# ARE_adaptadores.net
KiCad netlist of a schematic drawn in EAGLE
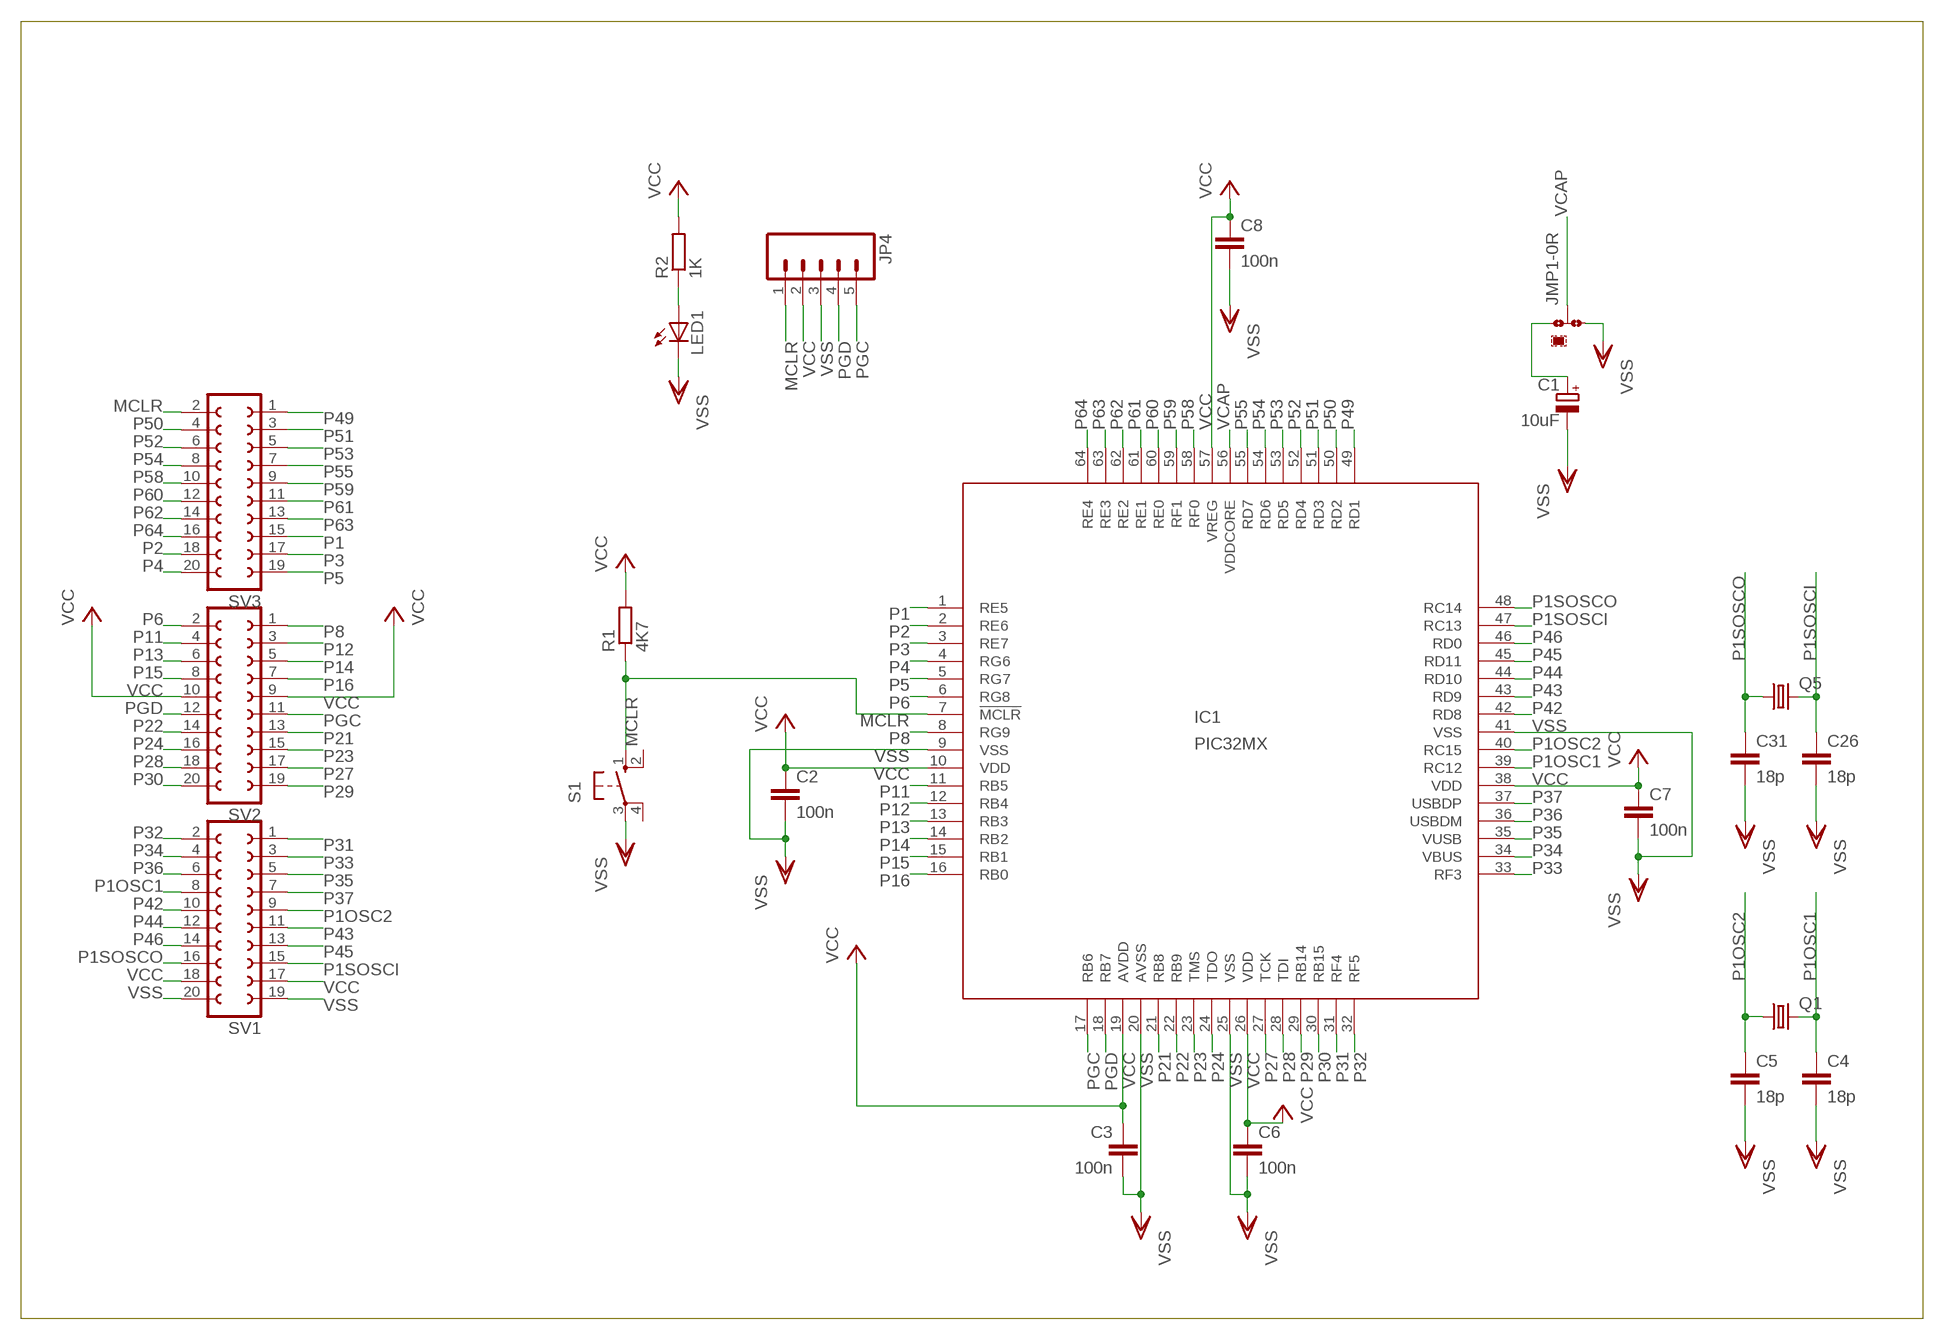
[diagram p0: schematic, sheet 1]
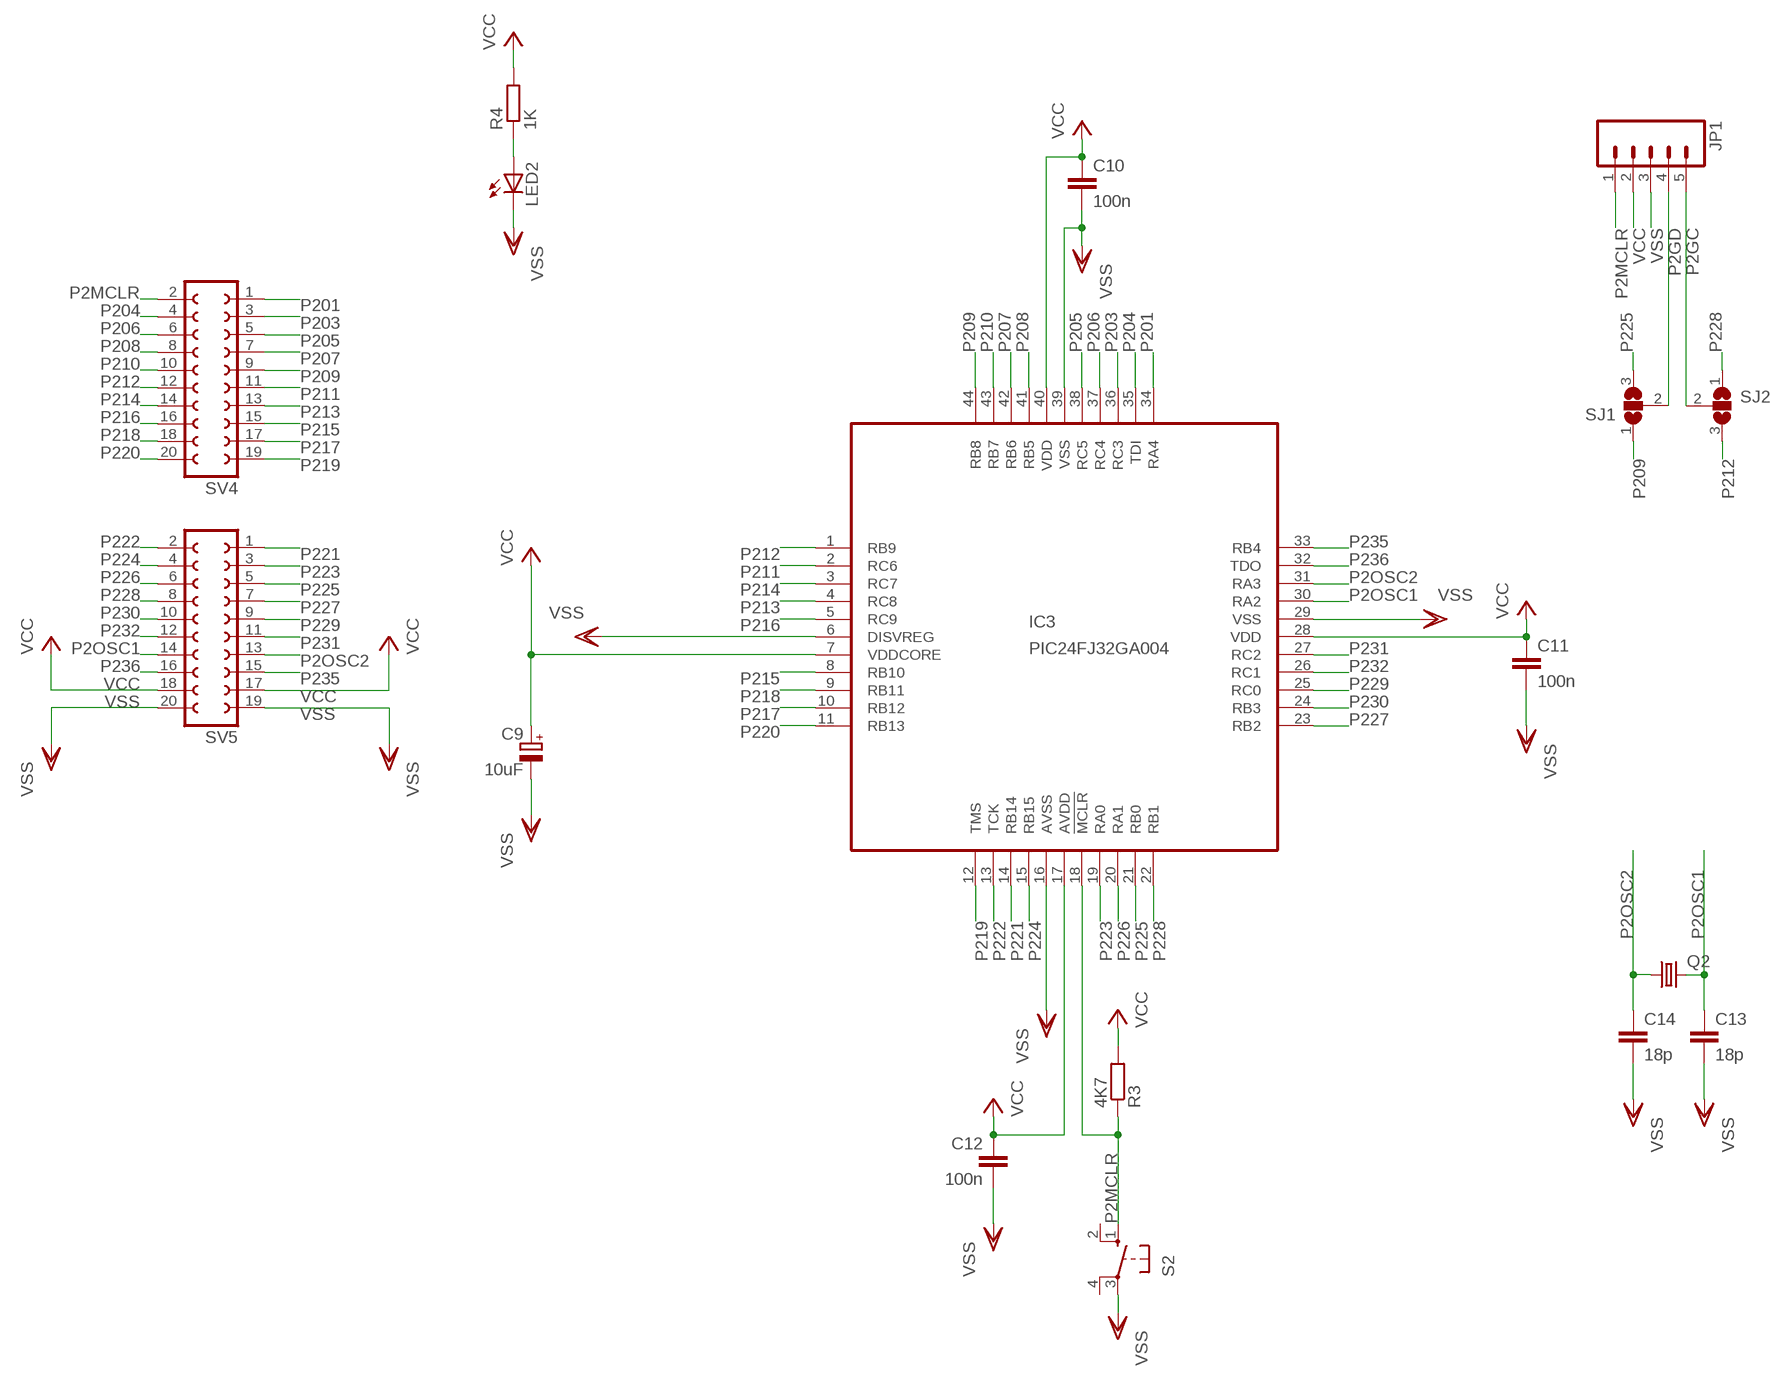
[diagram p1: schematic, sheet 2]
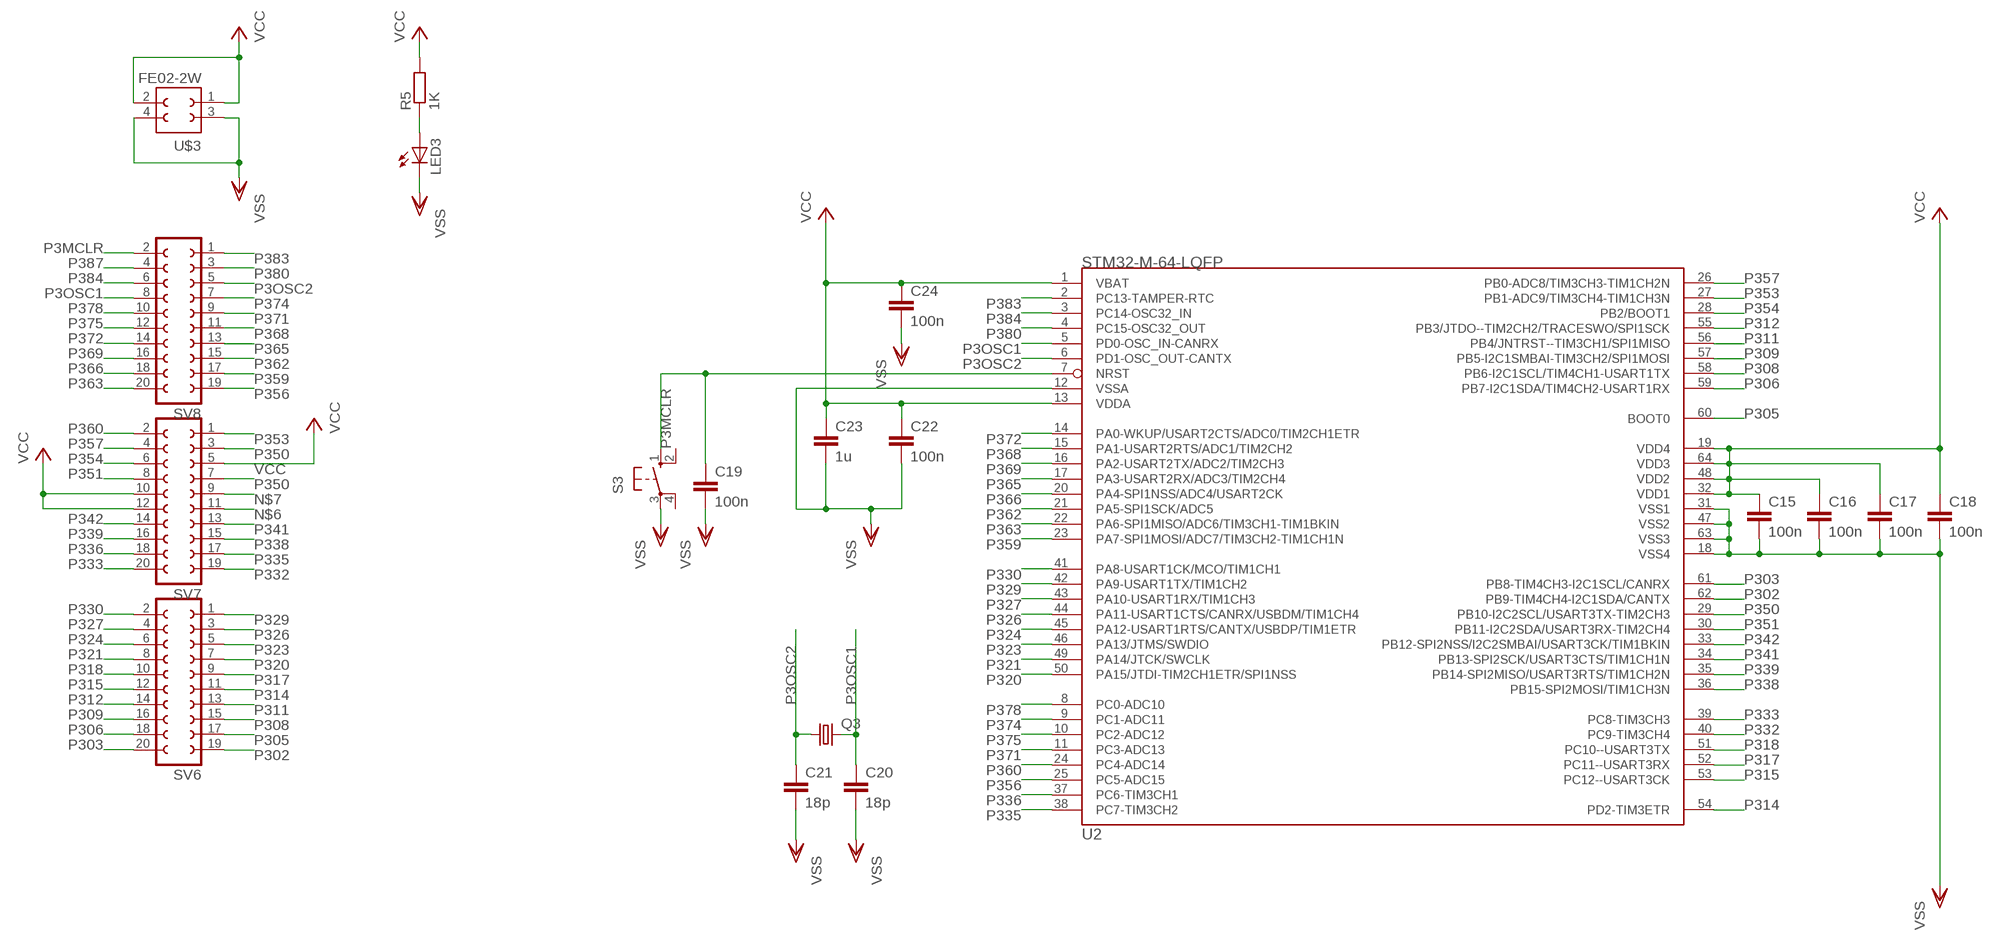
[diagram p2: schematic, sheet 3]
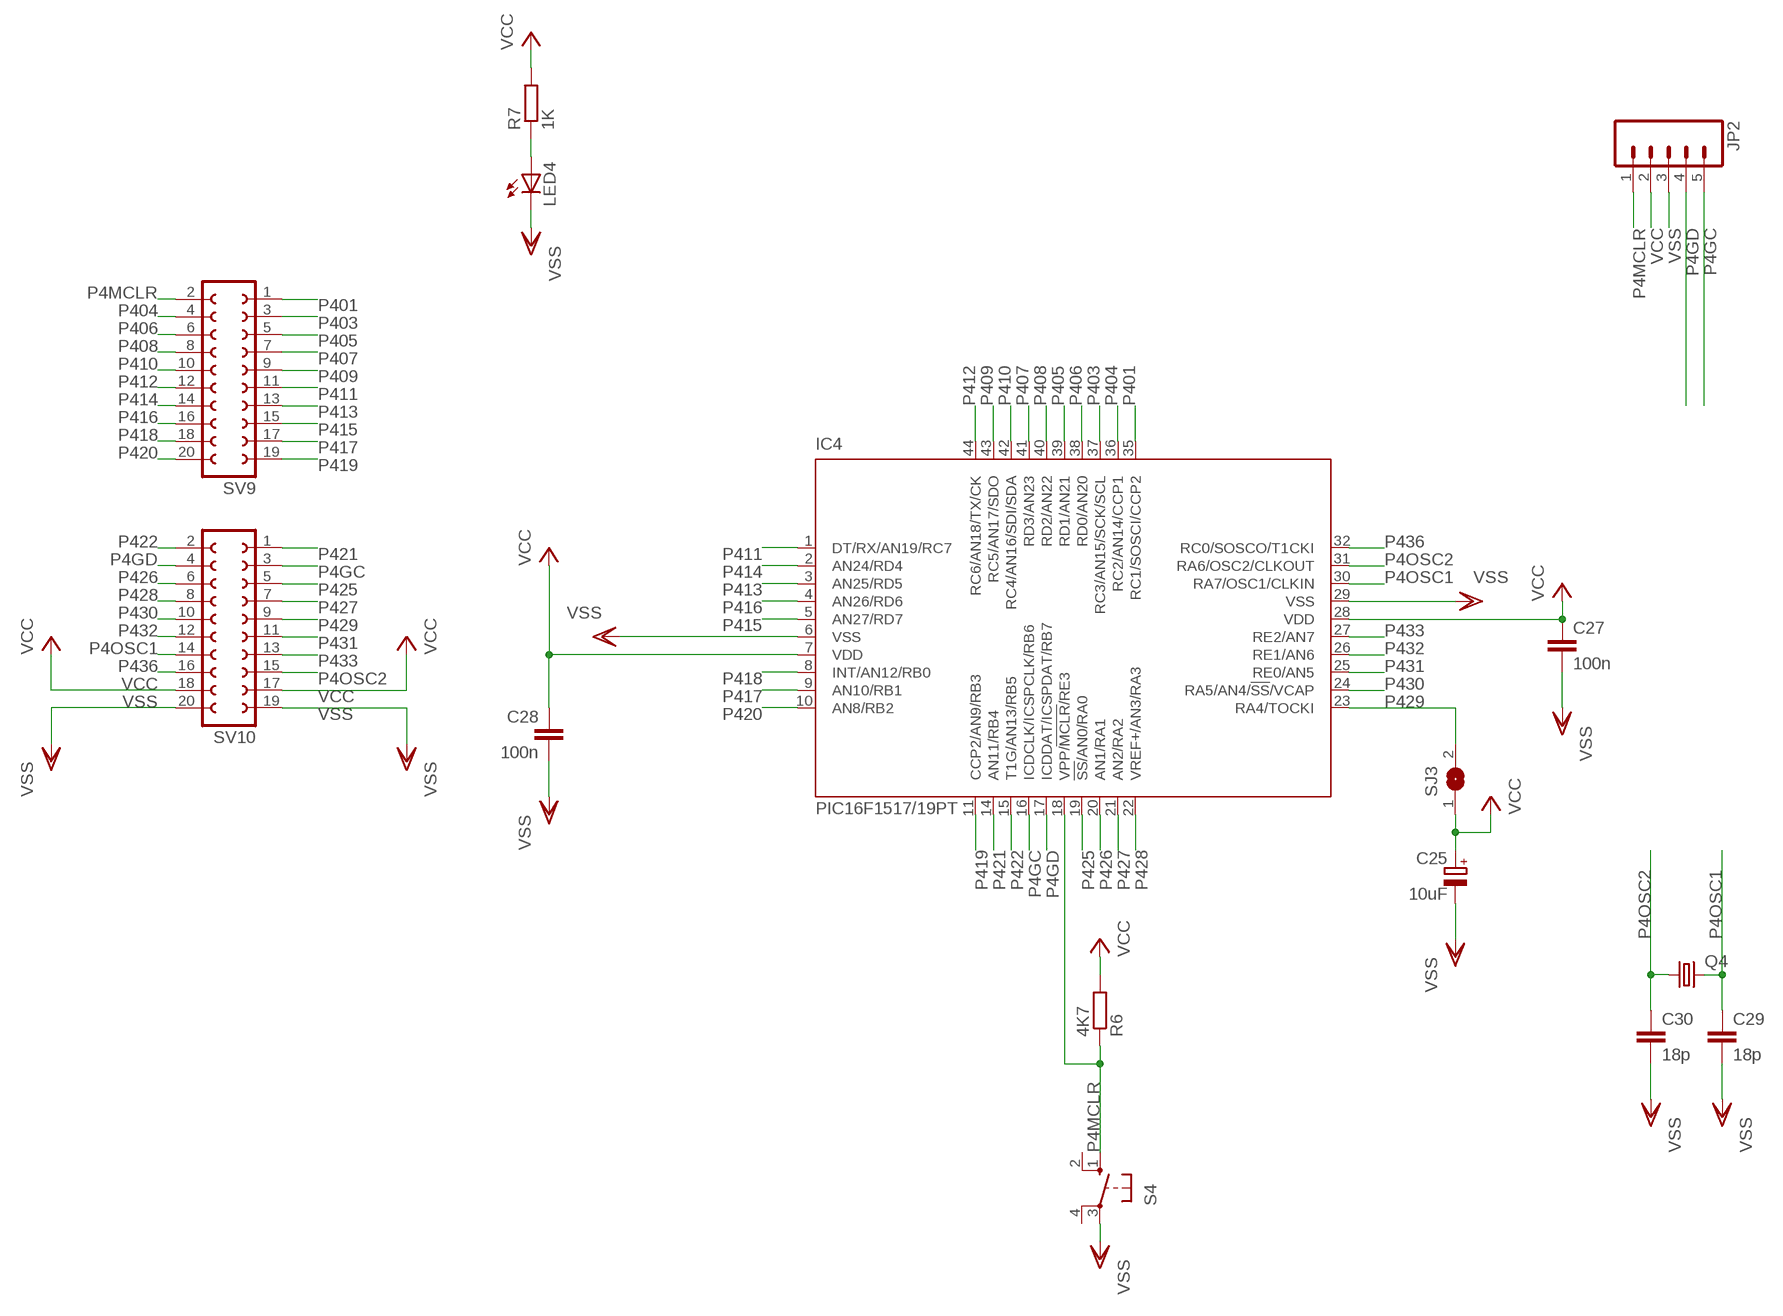
[diagram p3: schematic, sheet 4]
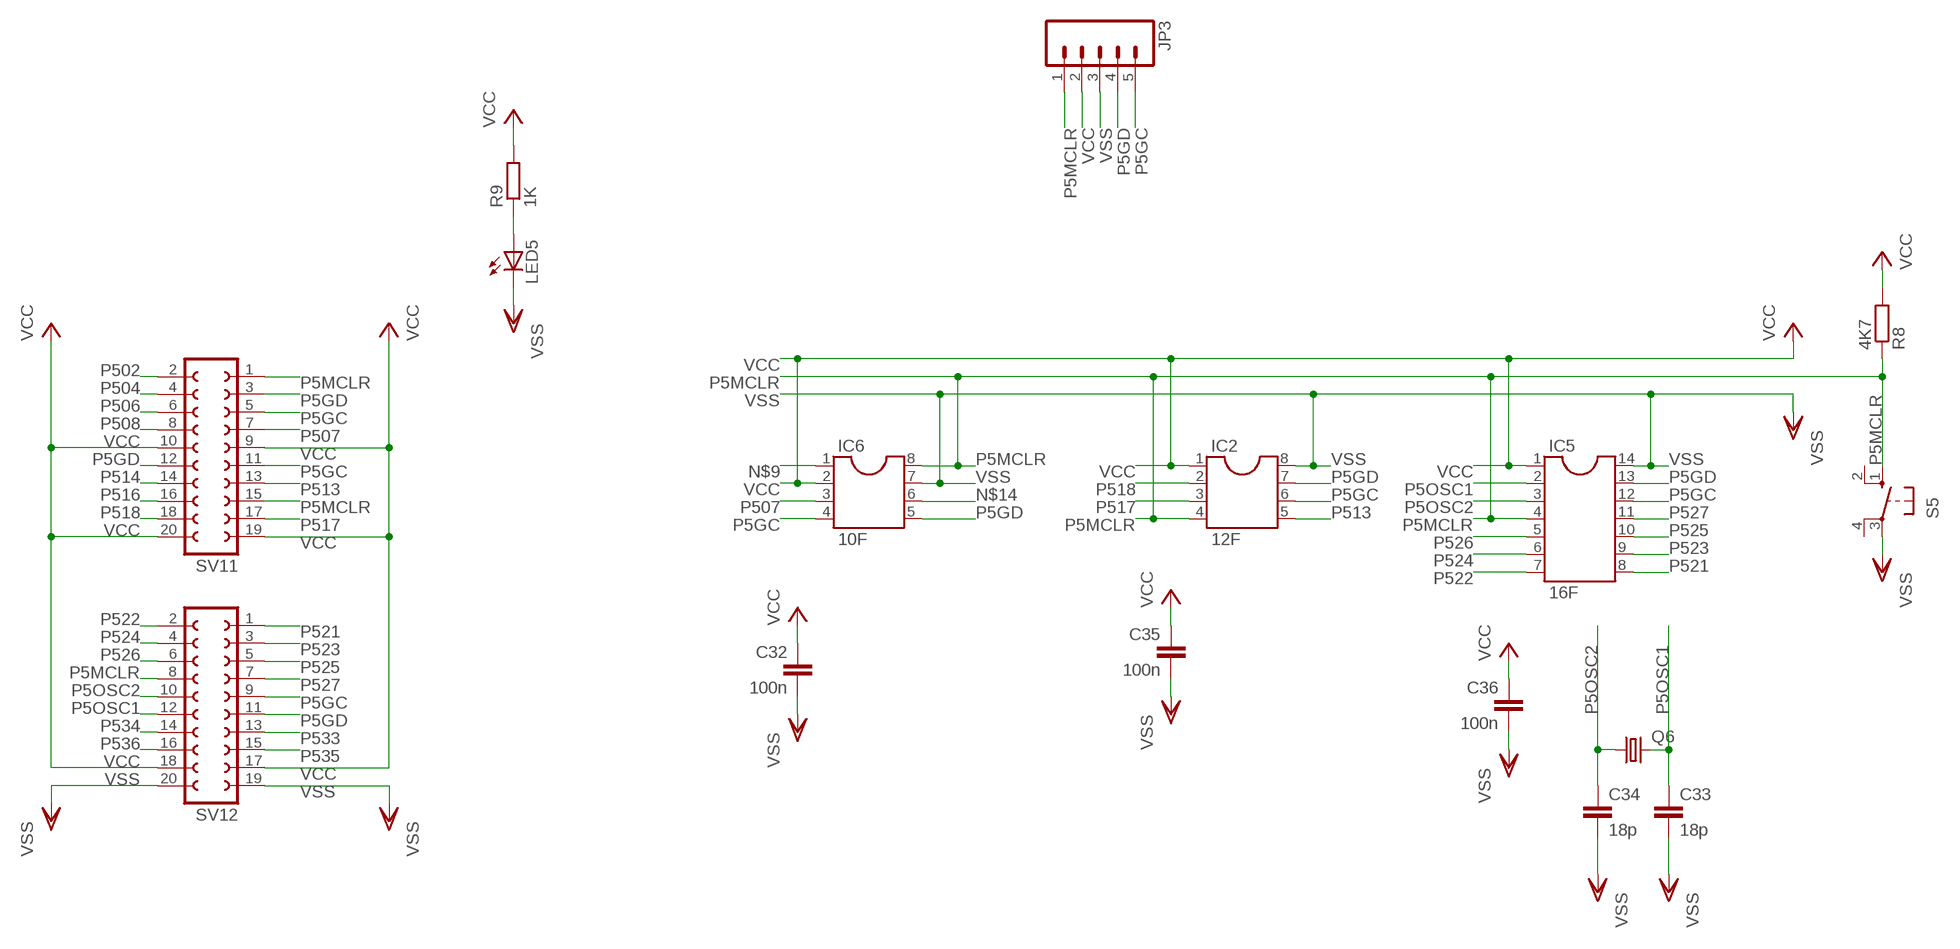
[diagram p4: schematic, sheet 5]

(export (version "E")
  (design (tool "Eeschema 10.0.6"))
  (components
    (comp (ref "C1")
      (value "10uF")
      (footprint "eagle-import:SMC_C")
      (libsource (lib "eagle-import") (part "CPOL-EUSMCC"))
    )
    (comp (ref "C2")
      (value "100n")
      (footprint "eagle-import:C0805")
      (libsource (lib "eagle-import") (part "C-EUC0805"))
    )
    (comp (ref "C3")
      (value "100n")
      (footprint "eagle-import:C0805")
      (libsource (lib "eagle-import") (part "C-EUC0805"))
    )
    (comp (ref "C4")
      (value "18p")
      (footprint "eagle-import:C0805")
      (libsource (lib "eagle-import") (part "C-EUC0805"))
    )
    (comp (ref "C5")
      (value "18p")
      (footprint "eagle-import:C0805")
      (libsource (lib "eagle-import") (part "C-EUC0805"))
    )
    (comp (ref "C6")
      (value "100n")
      (footprint "eagle-import:C0805")
      (libsource (lib "eagle-import") (part "C-EUC0805"))
    )
    (comp (ref "C7")
      (value "100n")
      (footprint "eagle-import:C0805")
      (libsource (lib "eagle-import") (part "C-EUC0805"))
    )
    (comp (ref "C8")
      (value "100n")
      (footprint "eagle-import:C0805")
      (libsource (lib "eagle-import") (part "C-EUC0805"))
    )
    (comp (ref "C26")
      (value "18p")
      (footprint "eagle-import:C0805")
      (libsource (lib "eagle-import") (part "C-EUC0805"))
    )
    (comp (ref "C31")
      (value "18p")
      (footprint "eagle-import:C0805")
      (libsource (lib "eagle-import") (part "C-EUC0805"))
    )
    (comp (ref "IC1")
      (value "PIC32MX")
      (footprint "eagle-import:TQFP64-10X10")
      (libsource (lib "eagle-import") (part "PIC32MX440F256H"))
    )
    (comp (ref "JMP1")
      (value "0R-JUMPA")
      (footprint "eagle-import:A0R-JMP")
      (libsource (lib "eagle-import") (part "0R-JUMPA"))
    )
    (comp (ref "JP4")
      (value "M05PTH")
      (footprint "eagle-import:1X05")
      (libsource (lib "eagle-import") (part "M05PTH"))
    )
    (comp (ref "LED1")
      (value "LEDCHIPLED_0805")
      (footprint "eagle-import:CHIPLED_0805")
      (libsource (lib "eagle-import") (part "LEDCHIPLED_0805"))
    )
    (comp (ref "Q1")
      (value "CRYSTALHC18U-V")
      (footprint "eagle-import:HC18U-V")
      (libsource (lib "eagle-import") (part "CRYSTALHC18U-V"))
    )
    (comp (ref "Q5")
      (value "CRYSTALHC18U-V")
      (footprint "eagle-import:HC18U-V")
      (libsource (lib "eagle-import") (part "CRYSTALHC18U-V"))
    )
    (comp (ref "R1")
      (value "4K7")
      (footprint "eagle-import:R0805")
      (libsource (lib "eagle-import") (part "R-EU_R0805"))
    )
    (comp (ref "R2")
      (value "1K")
      (footprint "eagle-import:R0805")
      (libsource (lib "eagle-import") (part "R-EU_R0805"))
    )
    (comp (ref "S1")
      (value "10-XX")
      (footprint "eagle-import:B3F-10XX")
      (fields
        (field (name "MPN") "B3F-1000")
        (field (name "MPN_1") "B3F-1000")
        (field (name "OC_FARNELL") "176432")
        (field (name "OC_NEWARK") "36M3542")
      )
      (libsource (lib "eagle-import") (part "10-XX"))
    )
    (comp (ref "SV1")
      (value "FE10-2W")
      (footprint "eagle-import:FE10-2W")
      (libsource (lib "eagle-import") (part "FE10-2W"))
    )
    (comp (ref "SV2")
      (value "FE10-2W")
      (footprint "eagle-import:FE10-2W")
      (libsource (lib "eagle-import") (part "FE10-2W"))
    )
    (comp (ref "SV3")
      (value "FE10-2W")
      (footprint "eagle-import:FE10-2W")
      (libsource (lib "eagle-import") (part "FE10-2W"))
    )
    (comp (ref "C15")
      (value "100n")
      (footprint "eagle-import:C0805")
      (libsource (lib "eagle-import") (part "C-EUC0805"))
    )
    (comp (ref "C16")
      (value "100n")
      (footprint "eagle-import:C0805")
      (libsource (lib "eagle-import") (part "C-EUC0805"))
    )
    (comp (ref "C17")
      (value "100n")
      (footprint "eagle-import:C0805")
      (libsource (lib "eagle-import") (part "C-EUC0805"))
    )
    (comp (ref "C18")
      (value "100n")
      (footprint "eagle-import:C0805")
      (libsource (lib "eagle-import") (part "C-EUC0805"))
    )
    (comp (ref "C19")
      (value "100n")
      (footprint "eagle-import:C0805")
      (libsource (lib "eagle-import") (part "C-EUC0805"))
    )
    (comp (ref "C20")
      (value "18p")
      (footprint "eagle-import:C0805")
      (libsource (lib "eagle-import") (part "C-EUC0805"))
    )
    (comp (ref "C21")
      (value "18p")
      (footprint "eagle-import:C0805")
      (libsource (lib "eagle-import") (part "C-EUC0805"))
    )
    (comp (ref "C22")
      (value "100n")
      (footprint "eagle-import:C0805")
      (libsource (lib "eagle-import") (part "C-EUC0805"))
    )
    (comp (ref "C23")
      (value "1u")
      (footprint "eagle-import:C0805")
      (libsource (lib "eagle-import") (part "C-EUC0805"))
    )
    (comp (ref "C24")
      (value "100n")
      (footprint "eagle-import:C0805")
      (libsource (lib "eagle-import") (part "C-EUC0805"))
    )
    (comp (ref "LED3")
      (value "LEDCHIPLED_0805")
      (footprint "eagle-import:CHIPLED_0805")
      (libsource (lib "eagle-import") (part "LEDCHIPLED_0805"))
    )
    (comp (ref "Q3")
      (value "CRYSTALHC18U-V")
      (footprint "eagle-import:HC18U-V")
      (libsource (lib "eagle-import") (part "CRYSTALHC18U-V"))
    )
    (comp (ref "R5")
      (value "1K")
      (footprint "eagle-import:R0805")
      (libsource (lib "eagle-import") (part "R-EU_R0805"))
    )
    (comp (ref "S3")
      (value "10-XX")
      (footprint "eagle-import:B3F-10XX")
      (fields
        (field (name "MPN") "B3F-1000")
        (field (name "MPN_1") "B3F-1000")
        (field (name "OC_FARNELL") "176432")
        (field (name "OC_NEWARK") "36M3542")
      )
      (libsource (lib "eagle-import") (part "10-XX"))
    )
    (comp (ref "SV6")
      (value "FE10-2W")
      (footprint "eagle-import:FE10-2W")
      (libsource (lib "eagle-import") (part "FE10-2W"))
    )
    (comp (ref "SV7")
      (value "FE10-2W")
      (footprint "eagle-import:FE10-2W")
      (libsource (lib "eagle-import") (part "FE10-2W"))
    )
    (comp (ref "SV8")
      (value "FE10-2W")
      (footprint "eagle-import:FE10-2W")
      (libsource (lib "eagle-import") (part "FE10-2W"))
    )
    (comp (ref "U$3")
      (value "FE02-2W")
      (footprint "eagle-import:FE02-2W")
      (libsource (lib "eagle-import") (part "FE02-2W"))
    )
    (comp (ref "U2")
      (value "STM32-M-64-LQFP")
      (footprint "eagle-import:LQFP64")
      (libsource (lib "eagle-import") (part "STM32-M-64-LQFP"))
    )
    (comp (ref "C25")
      (value "10uF")
      (footprint "eagle-import:SMC_C")
      (libsource (lib "eagle-import") (part "CPOL-EUSMCC"))
    )
    (comp (ref "C27")
      (value "100n")
      (footprint "eagle-import:C0805")
      (libsource (lib "eagle-import") (part "C-EUC0805"))
    )
    (comp (ref "C28")
      (value "100n")
      (footprint "eagle-import:C0805")
      (libsource (lib "eagle-import") (part "C-EUC0805"))
    )
    (comp (ref "C29")
      (value "18p")
      (footprint "eagle-import:C0805")
      (libsource (lib "eagle-import") (part "C-EUC0805"))
    )
    (comp (ref "C30")
      (value "18p")
      (footprint "eagle-import:C0805")
      (libsource (lib "eagle-import") (part "C-EUC0805"))
    )
    (comp (ref "IC4")
      (value "PIC16F1517/19PT")
      (footprint "eagle-import:TQFP44")
      (libsource (lib "eagle-import") (part "PIC16F1517/19PT"))
    )
    (comp (ref "JP2")
      (value "M05PTH")
      (footprint "eagle-import:1X05")
      (libsource (lib "eagle-import") (part "M05PTH"))
    )
    (comp (ref "LED4")
      (value "LEDCHIPLED_0805")
      (footprint "eagle-import:CHIPLED_0805")
      (libsource (lib "eagle-import") (part "LEDCHIPLED_0805"))
    )
    (comp (ref "Q4")
      (value "CRYSTALHC18U-V")
      (footprint "eagle-import:HC18U-V")
      (libsource (lib "eagle-import") (part "CRYSTALHC18U-V"))
    )
    (comp (ref "R6")
      (value "4K7")
      (footprint "eagle-import:R0805")
      (libsource (lib "eagle-import") (part "R-EU_R0805"))
    )
    (comp (ref "R7")
      (value "1K")
      (footprint "eagle-import:R0805")
      (libsource (lib "eagle-import") (part "R-EU_R0805"))
    )
    (comp (ref "S4")
      (value "10-XX")
      (footprint "eagle-import:B3F-10XX")
      (fields
        (field (name "MPN") "B3F-1000")
        (field (name "MPN_1") "B3F-1000")
        (field (name "OC_FARNELL") "176432")
        (field (name "OC_NEWARK") "36M3542")
      )
      (libsource (lib "eagle-import") (part "10-XX"))
    )
    (comp (ref "SJ3") (value "SJ") (footprint "eagle-import:SJ") (libsource (lib "eagle-import") (part "SJ")))
    (comp (ref "SV9")
      (value "FE10-2W")
      (footprint "eagle-import:FE10-2W")
      (libsource (lib "eagle-import") (part "FE10-2W"))
    )
    (comp (ref "SV10")
      (value "FE10-2W")
      (footprint "eagle-import:FE10-2W")
      (libsource (lib "eagle-import") (part "FE10-2W"))
    )
    (comp (ref "C32")
      (value "100n")
      (footprint "eagle-import:C0805")
      (libsource (lib "eagle-import") (part "C-EUC0805"))
    )
    (comp (ref "C33")
      (value "18p")
      (footprint "eagle-import:C0805")
      (libsource (lib "eagle-import") (part "C-EUC0805"))
    )
    (comp (ref "C34")
      (value "18p")
      (footprint "eagle-import:C0805")
      (libsource (lib "eagle-import") (part "C-EUC0805"))
    )
    (comp (ref "C35")
      (value "100n")
      (footprint "eagle-import:C0805")
      (libsource (lib "eagle-import") (part "C-EUC0805"))
    )
    (comp (ref "C36")
      (value "100n")
      (footprint "eagle-import:C0805")
      (libsource (lib "eagle-import") (part "C-EUC0805"))
    )
    (comp (ref "IC2")
      (value "12F")
      (footprint "eagle-import:SOCKET-08")
      (libsource (lib "eagle-import") (part "DIL8S"))
    )
    (comp (ref "IC5")
      (value "16F")
      (footprint "eagle-import:SOCKET-14")
      (libsource (lib "eagle-import") (part "DIL14S"))
    )
    (comp (ref "IC6")
      (value "10F")
      (footprint "eagle-import:SOCKET-08")
      (libsource (lib "eagle-import") (part "DIL8S"))
    )
    (comp (ref "JP3")
      (value "M05PTH")
      (footprint "eagle-import:1X05")
      (libsource (lib "eagle-import") (part "M05PTH"))
    )
    (comp (ref "LED5")
      (value "LEDCHIPLED_0805")
      (footprint "eagle-import:CHIPLED_0805")
      (libsource (lib "eagle-import") (part "LEDCHIPLED_0805"))
    )
    (comp (ref "Q6")
      (value "CRYSTALHC18U-V")
      (footprint "eagle-import:HC18U-V")
      (libsource (lib "eagle-import") (part "CRYSTALHC18U-V"))
    )
    (comp (ref "R8")
      (value "4K7")
      (footprint "eagle-import:R0805")
      (libsource (lib "eagle-import") (part "R-EU_R0805"))
    )
    (comp (ref "R9")
      (value "1K")
      (footprint "eagle-import:R0805")
      (libsource (lib "eagle-import") (part "R-EU_R0805"))
    )
    (comp (ref "S5")
      (value "10-XX")
      (footprint "eagle-import:B3F-10XX")
      (fields
        (field (name "MPN") "B3F-1000")
        (field (name "MPN_1") "B3F-1000")
        (field (name "OC_FARNELL") "176432")
        (field (name "OC_NEWARK") "36M3542")
      )
      (libsource (lib "eagle-import") (part "10-XX"))
    )
    (comp (ref "SV11")
      (value "FE10-2W")
      (footprint "eagle-import:FE10-2W")
      (libsource (lib "eagle-import") (part "FE10-2W"))
    )
    (comp (ref "SV12")
      (value "FE10-2W")
      (footprint "eagle-import:FE10-2W")
      (libsource (lib "eagle-import") (part "FE10-2W"))
    )
    (comp (ref "C9")
      (value "10uF")
      (footprint "eagle-import:SMC_C")
      (libsource (lib "eagle-import") (part "CPOL-EUSMCC"))
    )
    (comp (ref "C10")
      (value "100n")
      (footprint "eagle-import:C0805")
      (libsource (lib "eagle-import") (part "C-EUC0805"))
    )
    (comp (ref "C11")
      (value "100n")
      (footprint "eagle-import:C0805")
      (libsource (lib "eagle-import") (part "C-EUC0805"))
    )
    (comp (ref "C12")
      (value "100n")
      (footprint "eagle-import:C0805")
      (libsource (lib "eagle-import") (part "C-EUC0805"))
    )
    (comp (ref "C13")
      (value "18p")
      (footprint "eagle-import:C0805")
      (libsource (lib "eagle-import") (part "C-EUC0805"))
    )
    (comp (ref "C14")
      (value "18p")
      (footprint "eagle-import:C0805")
      (libsource (lib "eagle-import") (part "C-EUC0805"))
    )
    (comp (ref "IC3")
      (value "PIC24FJ32GA004")
      (footprint "eagle-import:TQFP44")
      (fields (field (name "MPN") "PIC24FJ32GA004-E/PT"))
      (libsource (lib "eagle-import") (part "PIC24FJ32GA004"))
    )
    (comp (ref "JP1")
      (value "M05PTH")
      (footprint "eagle-import:1X05")
      (libsource (lib "eagle-import") (part "M05PTH"))
    )
    (comp (ref "LED2")
      (value "LEDCHIPLED_0805")
      (footprint "eagle-import:CHIPLED_0805")
      (libsource (lib "eagle-import") (part "LEDCHIPLED_0805"))
    )
    (comp (ref "Q2")
      (value "CRYSTALHC18U-V")
      (footprint "eagle-import:HC18U-V")
      (libsource (lib "eagle-import") (part "CRYSTALHC18U-V"))
    )
    (comp (ref "R3")
      (value "4K7")
      (footprint "eagle-import:R0805")
      (libsource (lib "eagle-import") (part "R-EU_R0805"))
    )
    (comp (ref "R4")
      (value "1K")
      (footprint "eagle-import:R0805")
      (libsource (lib "eagle-import") (part "R-EU_R0805"))
    )
    (comp (ref "S2")
      (value "10-XX")
      (footprint "eagle-import:B3F-10XX")
      (fields
        (field (name "MPN") "B3F-1000")
        (field (name "MPN_1") "B3F-1000")
        (field (name "OC_FARNELL") "176432")
        (field (name "OC_NEWARK") "36M3542")
      )
      (libsource (lib "eagle-import") (part "10-XX"))
    )
    (comp (ref "SJ1")
      (value "SJ2W")
      (footprint "eagle-import:SJ_2")
      (libsource (lib "eagle-import") (part "SJ2W"))
    )
    (comp (ref "SJ2")
      (value "SJ2W")
      (footprint "eagle-import:SJ_2")
      (libsource (lib "eagle-import") (part "SJ2W"))
    )
    (comp (ref "SV4")
      (value "FE10-2W")
      (footprint "eagle-import:FE10-2W")
      (libsource (lib "eagle-import") (part "FE10-2W"))
    )
    (comp (ref "SV5")
      (value "FE10-2W")
      (footprint "eagle-import:FE10-2W")
      (libsource (lib "eagle-import") (part "FE10-2W"))
    )
  )
  (nets
    (net (code "1") (name "MCLR") (class "Default")
      (node (ref "IC1") (pin "7") (pinfunction "~{MCLR}_7") (pintype "input"))
      (node (ref "JP4") (pin "1") (pinfunction "1_1") (pintype "passive"))
      (node (ref "R1") (pin "1") (pinfunction "1_1") (pintype "passive"))
      (node (ref "S1") (pin "1") (pinfunction "S_1") (pintype "passive"))
      (node (ref "SV3") (pin "2") (pinfunction "2_2") (pintype "passive"))
    )
    (net (code "2") (name "N$6") (class "Default")
      (node (ref "SV7") (pin "11") (pinfunction "11_11") (pintype "passive"))
    )
    (net (code "3") (name "N$7") (class "Default")
      (node (ref "SV7") (pin "9") (pinfunction "9_9") (pintype "passive"))
    )
    (net (code "4") (name "N$9") (class "Default")
      (node (ref "IC6") (pin "1") (pinfunction "1_1") (pintype "passive"))
    )
    (net (code "5") (name "N$14") (class "Default")
      (node (ref "IC6") (pin "6") (pinfunction "6_6") (pintype "passive"))
    )
    (net (code "6") (name "Net-(C1-Pad+)") (class "Default")
      (node (ref "C1") (pin "+") (pinfunction "+_+") (pintype "passive"))
      (node (ref "JMP1") (pin "1") (pinfunction "1_1") (pintype "passive"))
    )
    (net (code "7") (name "Net-(LED1-PadA)") (class "Default")
      (node (ref "LED1") (pin "A") (pinfunction "A_A") (pintype "passive"))
      (node (ref "R2") (pin "1") (pinfunction "1_1") (pintype "passive"))
    )
    (net (code "8") (name "Net-(LED2-PadA)") (class "Default")
      (node (ref "LED2") (pin "A") (pinfunction "A_A") (pintype "passive"))
      (node (ref "R4") (pin "1") (pinfunction "1_1") (pintype "passive"))
    )
    (net (code "9") (name "Net-(LED3-PadA)") (class "Default")
      (node (ref "LED3") (pin "A") (pinfunction "A_A") (pintype "passive"))
      (node (ref "R5") (pin "1") (pinfunction "1_1") (pintype "passive"))
    )
    (net (code "10") (name "Net-(LED4-PadA)") (class "Default")
      (node (ref "LED4") (pin "A") (pinfunction "A_A") (pintype "passive"))
      (node (ref "R7") (pin "1") (pinfunction "1_1") (pintype "passive"))
    )
    (net (code "11") (name "Net-(LED5-PadA)") (class "Default")
      (node (ref "LED5") (pin "A") (pinfunction "A_A") (pintype "passive"))
      (node (ref "R9") (pin "1") (pinfunction "1_1") (pintype "passive"))
    )
    (net (code "12") (name "P1") (class "Default")
      (node (ref "IC1") (pin "1") (pinfunction "RE5_1") (pintype "bidirectional"))
      (node (ref "SV3") (pin "15") (pinfunction "15_15") (pintype "passive"))
    )
    (net (code "13") (name "P1OSC1") (class "Default")
      (node (ref "C4") (pin "1") (pinfunction "1_1") (pintype "passive"))
      (node (ref "IC1") (pin "39") (pinfunction "RC12_39") (pintype "bidirectional"))
      (node (ref "Q1") (pin "2") (pinfunction "2_2") (pintype "passive"))
      (node (ref "SV1") (pin "8") (pinfunction "8_8") (pintype "passive"))
    )
    (net (code "14") (name "P1OSC2") (class "Default")
      (node (ref "C5") (pin "1") (pinfunction "1_1") (pintype "passive"))
      (node (ref "IC1") (pin "40") (pinfunction "RC15_40") (pintype "bidirectional"))
      (node (ref "Q1") (pin "1") (pinfunction "1_1") (pintype "passive"))
      (node (ref "SV1") (pin "9") (pinfunction "9_9") (pintype "passive"))
    )
    (net (code "15") (name "P1SOSCI") (class "Default")
      (node (ref "C26") (pin "1") (pinfunction "1_1") (pintype "passive"))
      (node (ref "IC1") (pin "47") (pinfunction "RC13_47") (pintype "bidirectional"))
      (node (ref "Q5") (pin "2") (pinfunction "2_2") (pintype "passive"))
      (node (ref "SV1") (pin "15") (pinfunction "15_15") (pintype "passive"))
    )
    (net (code "16") (name "P1SOSCO") (class "Default")
      (node (ref "C31") (pin "1") (pinfunction "1_1") (pintype "passive"))
      (node (ref "IC1") (pin "48") (pinfunction "RC14_48") (pintype "bidirectional"))
      (node (ref "Q5") (pin "1") (pinfunction "1_1") (pintype "passive"))
      (node (ref "SV1") (pin "16") (pinfunction "16_16") (pintype "passive"))
    )
    (net (code "17") (name "P2") (class "Default")
      (node (ref "IC1") (pin "2") (pinfunction "RE6_2") (pintype "bidirectional"))
      (node (ref "SV3") (pin "18") (pinfunction "18_18") (pintype "passive"))
    )
    (net (code "18") (name "P2GC") (class "Default")
      (node (ref "JP1") (pin "5") (pinfunction "5_5") (pintype "passive"))
      (node (ref "SJ2") (pin "2") (pinfunction "2_2") (pintype "passive"))
    )
    (net (code "19") (name "P2GD") (class "Default")
      (node (ref "JP1") (pin "4") (pinfunction "4_4") (pintype "passive"))
      (node (ref "SJ1") (pin "2") (pinfunction "2_2") (pintype "passive"))
    )
    (net (code "20") (name "P2MCLR") (class "Default")
      (node (ref "IC3") (pin "18") (pinfunction "~{MCLR}_18") (pintype "bidirectional"))
      (node (ref "JP1") (pin "1") (pinfunction "1_1") (pintype "passive"))
      (node (ref "R3") (pin "1") (pinfunction "1_1") (pintype "passive"))
      (node (ref "S2") (pin "1") (pinfunction "S_1") (pintype "passive"))
      (node (ref "SV4") (pin "2") (pinfunction "2_2") (pintype "passive"))
    )
    (net (code "21") (name "P2OSC1") (class "Default")
      (node (ref "C13") (pin "1") (pinfunction "1_1") (pintype "passive"))
      (node (ref "IC3") (pin "30") (pinfunction "RA2_30") (pintype "bidirectional"))
      (node (ref "Q2") (pin "2") (pinfunction "2_2") (pintype "passive"))
      (node (ref "SV5") (pin "14") (pinfunction "14_14") (pintype "passive"))
    )
    (net (code "22") (name "P2OSC2") (class "Default")
      (node (ref "C14") (pin "1") (pinfunction "1_1") (pintype "passive"))
      (node (ref "IC3") (pin "31") (pinfunction "RA3_31") (pintype "bidirectional"))
      (node (ref "Q2") (pin "1") (pinfunction "1_1") (pintype "passive"))
      (node (ref "SV5") (pin "13") (pinfunction "13_13") (pintype "passive"))
    )
    (net (code "23") (name "P3") (class "Default")
      (node (ref "IC1") (pin "3") (pinfunction "RE7_3") (pintype "bidirectional"))
      (node (ref "SV3") (pin "17") (pinfunction "17_17") (pintype "passive"))
    )
    (net (code "24") (name "P3MCLR") (class "Default")
      (node (ref "C19") (pin "1") (pinfunction "1_1") (pintype "passive"))
      (node (ref "S3") (pin "1") (pinfunction "S_1") (pintype "passive"))
      (node (ref "SV8") (pin "2") (pinfunction "2_2") (pintype "passive"))
      (node (ref "U2") (pin "7") (pinfunction "NRST_7") (pintype "bidirectional"))
    )
    (net (code "25") (name "P3OSC1") (class "Default")
      (node (ref "C20") (pin "1") (pinfunction "1_1") (pintype "passive"))
      (node (ref "Q3") (pin "2") (pinfunction "2_2") (pintype "passive"))
      (node (ref "SV8") (pin "8") (pinfunction "8_8") (pintype "passive"))
      (node (ref "U2") (pin "5") (pinfunction "PD0-OSC_IN-CANRX_5") (pintype "input"))
    )
    (net (code "26") (name "P3OSC2") (class "Default")
      (node (ref "C21") (pin "1") (pinfunction "1_1") (pintype "passive"))
      (node (ref "Q3") (pin "1") (pinfunction "1_1") (pintype "passive"))
      (node (ref "SV8") (pin "5") (pinfunction "5_5") (pintype "passive"))
      (node (ref "U2") (pin "6") (pinfunction "PD1-OSC_OUT-CANTX_6") (pintype "output"))
    )
    (net (code "27") (name "P4") (class "Default")
      (node (ref "IC1") (pin "4") (pinfunction "RG6_4") (pintype "bidirectional"))
      (node (ref "SV3") (pin "20") (pinfunction "20_20") (pintype "passive"))
    )
    (net (code "28") (name "P4GC") (class "Default")
      (node (ref "IC4") (pin "16") (pinfunction "ICDCLK/ICSPCLK/RB6_16") (pintype "bidirectional"))
      (node (ref "JP2") (pin "5") (pinfunction "5_5") (pintype "passive"))
      (node (ref "SV10") (pin "3") (pinfunction "3_3") (pintype "passive"))
    )
    (net (code "29") (name "P4GD") (class "Default")
      (node (ref "IC4") (pin "17") (pinfunction "ICDDAT/ICSPDAT/RB7_17") (pintype "bidirectional"))
      (node (ref "JP2") (pin "4") (pinfunction "4_4") (pintype "passive"))
      (node (ref "SV10") (pin "4") (pinfunction "4_4") (pintype "passive"))
    )
    (net (code "30") (name "P4MCLR") (class "Default")
      (node (ref "IC4") (pin "18") (pinfunction "VPP/~{MCLR}/RE3_18") (pintype "input"))
      (node (ref "JP2") (pin "1") (pinfunction "1_1") (pintype "passive"))
      (node (ref "R6") (pin "1") (pinfunction "1_1") (pintype "passive"))
      (node (ref "S4") (pin "1") (pinfunction "S_1") (pintype "passive"))
      (node (ref "SV9") (pin "2") (pinfunction "2_2") (pintype "passive"))
    )
    (net (code "31") (name "P4OSC1") (class "Default")
      (node (ref "C29") (pin "1") (pinfunction "1_1") (pintype "passive"))
      (node (ref "IC4") (pin "30") (pinfunction "RA7/OSC1/CLKIN_30") (pintype "bidirectional"))
      (node (ref "Q4") (pin "2") (pinfunction "2_2") (pintype "passive"))
      (node (ref "SV10") (pin "14") (pinfunction "14_14") (pintype "passive"))
    )
    (net (code "32") (name "P4OSC2") (class "Default")
      (node (ref "C30") (pin "1") (pinfunction "1_1") (pintype "passive"))
      (node (ref "IC4") (pin "31") (pinfunction "RA6/OSC2/CLKOUT_31") (pintype "bidirectional"))
      (node (ref "Q4") (pin "1") (pinfunction "1_1") (pintype "passive"))
      (node (ref "SV10") (pin "15") (pinfunction "15_15") (pintype "passive"))
    )
    (net (code "33") (name "P5") (class "Default")
      (node (ref "IC1") (pin "5") (pinfunction "RG7_5") (pintype "bidirectional"))
      (node (ref "SV3") (pin "19") (pinfunction "19_19") (pintype "passive"))
    )
    (net (code "34") (name "P5GC") (class "Default")
      (node (ref "IC2") (pin "6") (pinfunction "6_6") (pintype "passive"))
      (node (ref "IC5") (pin "12") (pinfunction "12_12") (pintype "passive"))
      (node (ref "IC6") (pin "4") (pinfunction "4_4") (pintype "passive"))
      (node (ref "JP3") (pin "5") (pinfunction "5_5") (pintype "passive"))
      (node (ref "SV11") (pin "11") (pinfunction "11_11") (pintype "passive"))
      (node (ref "SV11") (pin "5") (pinfunction "5_5") (pintype "passive"))
      (node (ref "SV12") (pin "9") (pinfunction "9_9") (pintype "passive"))
    )
    (net (code "35") (name "P5GD") (class "Default")
      (node (ref "IC2") (pin "7") (pinfunction "7_7") (pintype "passive"))
      (node (ref "IC5") (pin "13") (pinfunction "13_13") (pintype "passive"))
      (node (ref "IC6") (pin "5") (pinfunction "5_5") (pintype "passive"))
      (node (ref "JP3") (pin "4") (pinfunction "4_4") (pintype "passive"))
      (node (ref "SV11") (pin "12") (pinfunction "12_12") (pintype "passive"))
      (node (ref "SV11") (pin "3") (pinfunction "3_3") (pintype "passive"))
      (node (ref "SV12") (pin "11") (pinfunction "11_11") (pintype "passive"))
    )
    (net (code "36") (name "P5MCLR") (class "Default")
      (node (ref "IC2") (pin "4") (pinfunction "4_4") (pintype "passive"))
      (node (ref "IC5") (pin "4") (pinfunction "4_4") (pintype "passive"))
      (node (ref "IC6") (pin "8") (pinfunction "8_8") (pintype "passive"))
      (node (ref "JP3") (pin "1") (pinfunction "1_1") (pintype "passive"))
      (node (ref "R8") (pin "1") (pinfunction "1_1") (pintype "passive"))
      (node (ref "S5") (pin "1") (pinfunction "S_1") (pintype "passive"))
      (node (ref "SV11") (pin "1") (pinfunction "1_1") (pintype "passive"))
      (node (ref "SV11") (pin "15") (pinfunction "15_15") (pintype "passive"))
      (node (ref "SV12") (pin "8") (pinfunction "8_8") (pintype "passive"))
    )
    (net (code "37") (name "P5OSC1") (class "Default")
      (node (ref "C33") (pin "1") (pinfunction "1_1") (pintype "passive"))
      (node (ref "IC5") (pin "2") (pinfunction "2_2") (pintype "passive"))
      (node (ref "Q6") (pin "2") (pinfunction "2_2") (pintype "passive"))
      (node (ref "SV12") (pin "12") (pinfunction "12_12") (pintype "passive"))
    )
    (net (code "38") (name "P5OSC2") (class "Default")
      (node (ref "C34") (pin "1") (pinfunction "1_1") (pintype "passive"))
      (node (ref "IC5") (pin "3") (pinfunction "3_3") (pintype "passive"))
      (node (ref "Q6") (pin "1") (pinfunction "1_1") (pintype "passive"))
      (node (ref "SV12") (pin "10") (pinfunction "10_10") (pintype "passive"))
    )
    (net (code "39") (name "P6") (class "Default")
      (node (ref "IC1") (pin "6") (pinfunction "RG8_6") (pintype "bidirectional"))
      (node (ref "SV2") (pin "2") (pinfunction "2_2") (pintype "passive"))
    )
    (net (code "40") (name "P8") (class "Default")
      (node (ref "IC1") (pin "8") (pinfunction "RG9_8") (pintype "bidirectional"))
      (node (ref "SV2") (pin "1") (pinfunction "1_1") (pintype "passive"))
    )
    (net (code "41") (name "P11") (class "Default")
      (node (ref "IC1") (pin "11") (pinfunction "RB5_11") (pintype "bidirectional"))
      (node (ref "SV2") (pin "4") (pinfunction "4_4") (pintype "passive"))
    )
    (net (code "42") (name "P12") (class "Default")
      (node (ref "IC1") (pin "12") (pinfunction "RB4_12") (pintype "bidirectional"))
      (node (ref "SV2") (pin "3") (pinfunction "3_3") (pintype "passive"))
    )
    (net (code "43") (name "P13") (class "Default")
      (node (ref "IC1") (pin "13") (pinfunction "RB3_13") (pintype "bidirectional"))
      (node (ref "SV2") (pin "6") (pinfunction "6_6") (pintype "passive"))
    )
    (net (code "44") (name "P14") (class "Default")
      (node (ref "IC1") (pin "14") (pinfunction "RB2_14") (pintype "bidirectional"))
      (node (ref "SV2") (pin "5") (pinfunction "5_5") (pintype "passive"))
    )
    (net (code "45") (name "P15") (class "Default")
      (node (ref "IC1") (pin "15") (pinfunction "RB1_15") (pintype "bidirectional"))
      (node (ref "SV2") (pin "8") (pinfunction "8_8") (pintype "passive"))
    )
    (net (code "46") (name "P16") (class "Default")
      (node (ref "IC1") (pin "16") (pinfunction "RB0_16") (pintype "bidirectional"))
      (node (ref "SV2") (pin "7") (pinfunction "7_7") (pintype "passive"))
    )
    (net (code "47") (name "P21") (class "Default")
      (node (ref "IC1") (pin "21") (pinfunction "RB8_21") (pintype "bidirectional"))
      (node (ref "SV2") (pin "13") (pinfunction "13_13") (pintype "passive"))
    )
    (net (code "48") (name "P22") (class "Default")
      (node (ref "IC1") (pin "22") (pinfunction "RB9_22") (pintype "bidirectional"))
      (node (ref "SV2") (pin "14") (pinfunction "14_14") (pintype "passive"))
    )
    (net (code "49") (name "P23") (class "Default")
      (node (ref "IC1") (pin "23") (pinfunction "TMS_23") (pintype "input"))
      (node (ref "SV2") (pin "15") (pinfunction "15_15") (pintype "passive"))
    )
    (net (code "50") (name "P24") (class "Default")
      (node (ref "IC1") (pin "24") (pinfunction "TDO_24") (pintype "output"))
      (node (ref "SV2") (pin "16") (pinfunction "16_16") (pintype "passive"))
    )
    (net (code "51") (name "P27") (class "Default")
      (node (ref "IC1") (pin "27") (pinfunction "TCK_27") (pintype "input"))
      (node (ref "SV2") (pin "17") (pinfunction "17_17") (pintype "passive"))
    )
    (net (code "52") (name "P28") (class "Default")
      (node (ref "IC1") (pin "28") (pinfunction "TDI_28") (pintype "input"))
      (node (ref "SV2") (pin "18") (pinfunction "18_18") (pintype "passive"))
    )
    (net (code "53") (name "P29") (class "Default")
      (node (ref "IC1") (pin "29") (pinfunction "RB14_29") (pintype "bidirectional"))
      (node (ref "SV2") (pin "19") (pinfunction "19_19") (pintype "passive"))
    )
    (net (code "54") (name "P30") (class "Default")
      (node (ref "IC1") (pin "30") (pinfunction "RB15_30") (pintype "bidirectional"))
      (node (ref "SV2") (pin "20") (pinfunction "20_20") (pintype "passive"))
    )
    (net (code "55") (name "P31") (class "Default")
      (node (ref "IC1") (pin "31") (pinfunction "RF4_31") (pintype "bidirectional"))
      (node (ref "SV1") (pin "1") (pinfunction "1_1") (pintype "passive"))
    )
    (net (code "56") (name "P32") (class "Default")
      (node (ref "IC1") (pin "32") (pinfunction "RF5_32") (pintype "bidirectional"))
      (node (ref "SV1") (pin "2") (pinfunction "2_2") (pintype "passive"))
    )
    (net (code "57") (name "P33") (class "Default")
      (node (ref "IC1") (pin "33") (pinfunction "RF3_33") (pintype "bidirectional"))
      (node (ref "SV1") (pin "3") (pinfunction "3_3") (pintype "passive"))
    )
    (net (code "58") (name "P34") (class "Default")
      (node (ref "IC1") (pin "34") (pinfunction "VBUS_34") (pintype "bidirectional"))
      (node (ref "SV1") (pin "4") (pinfunction "4_4") (pintype "passive"))
    )
    (net (code "59") (name "P35") (class "Default")
      (node (ref "IC1") (pin "35") (pinfunction "VUSB_35") (pintype "passive"))
      (node (ref "SV1") (pin "5") (pinfunction "5_5") (pintype "passive"))
    )
    (net (code "60") (name "P36") (class "Default")
      (node (ref "IC1") (pin "36") (pinfunction "USBDM_36") (pintype "bidirectional"))
      (node (ref "SV1") (pin "6") (pinfunction "6_6") (pintype "passive"))
    )
    (net (code "61") (name "P37") (class "Default")
      (node (ref "IC1") (pin "37") (pinfunction "USBDP_37") (pintype "bidirectional"))
      (node (ref "SV1") (pin "7") (pinfunction "7_7") (pintype "passive"))
    )
    (net (code "62") (name "P42") (class "Default")
      (node (ref "IC1") (pin "42") (pinfunction "RD8_42") (pintype "bidirectional"))
      (node (ref "SV1") (pin "10") (pinfunction "10_10") (pintype "passive"))
    )
    (net (code "63") (name "P43") (class "Default")
      (node (ref "IC1") (pin "43") (pinfunction "RD9_43") (pintype "bidirectional"))
      (node (ref "SV1") (pin "11") (pinfunction "11_11") (pintype "passive"))
    )
    (net (code "64") (name "P44") (class "Default")
      (node (ref "IC1") (pin "44") (pinfunction "RD10_44") (pintype "bidirectional"))
      (node (ref "SV1") (pin "12") (pinfunction "12_12") (pintype "passive"))
    )
    (net (code "65") (name "P45") (class "Default")
      (node (ref "IC1") (pin "45") (pinfunction "RD11_45") (pintype "bidirectional"))
      (node (ref "SV1") (pin "13") (pinfunction "13_13") (pintype "passive"))
    )
    (net (code "66") (name "P46") (class "Default")
      (node (ref "IC1") (pin "46") (pinfunction "RD0_46") (pintype "bidirectional"))
      (node (ref "SV1") (pin "14") (pinfunction "14_14") (pintype "passive"))
    )
    (net (code "67") (name "P49") (class "Default")
      (node (ref "IC1") (pin "49") (pinfunction "RD1_49") (pintype "bidirectional"))
      (node (ref "SV3") (pin "1") (pinfunction "1_1") (pintype "passive"))
    )
    (net (code "68") (name "P50") (class "Default")
      (node (ref "IC1") (pin "50") (pinfunction "RD2_50") (pintype "bidirectional"))
      (node (ref "SV3") (pin "4") (pinfunction "4_4") (pintype "passive"))
    )
    (net (code "69") (name "P51") (class "Default")
      (node (ref "IC1") (pin "51") (pinfunction "RD3_51") (pintype "bidirectional"))
      (node (ref "SV3") (pin "3") (pinfunction "3_3") (pintype "passive"))
    )
    (net (code "70") (name "P52") (class "Default")
      (node (ref "IC1") (pin "52") (pinfunction "RD4_52") (pintype "bidirectional"))
      (node (ref "SV3") (pin "6") (pinfunction "6_6") (pintype "passive"))
    )
    (net (code "71") (name "P53") (class "Default")
      (node (ref "IC1") (pin "53") (pinfunction "RD5_53") (pintype "bidirectional"))
      (node (ref "SV3") (pin "5") (pinfunction "5_5") (pintype "passive"))
    )
    (net (code "72") (name "P54") (class "Default")
      (node (ref "IC1") (pin "54") (pinfunction "RD6_54") (pintype "bidirectional"))
      (node (ref "SV3") (pin "8") (pinfunction "8_8") (pintype "passive"))
    )
    (net (code "73") (name "P55") (class "Default")
      (node (ref "IC1") (pin "55") (pinfunction "RD7_55") (pintype "bidirectional"))
      (node (ref "SV3") (pin "7") (pinfunction "7_7") (pintype "passive"))
    )
    (net (code "74") (name "P58") (class "Default")
      (node (ref "IC1") (pin "58") (pinfunction "RF0_58") (pintype "bidirectional"))
      (node (ref "SV3") (pin "10") (pinfunction "10_10") (pintype "passive"))
    )
    (net (code "75") (name "P59") (class "Default")
      (node (ref "IC1") (pin "59") (pinfunction "RF1_59") (pintype "bidirectional"))
      (node (ref "SV3") (pin "9") (pinfunction "9_9") (pintype "passive"))
    )
    (net (code "76") (name "P60") (class "Default")
      (node (ref "IC1") (pin "60") (pinfunction "RE0_60") (pintype "bidirectional"))
      (node (ref "SV3") (pin "12") (pinfunction "12_12") (pintype "passive"))
    )
    (net (code "77") (name "P61") (class "Default")
      (node (ref "IC1") (pin "61") (pinfunction "RE1_61") (pintype "bidirectional"))
      (node (ref "SV3") (pin "11") (pinfunction "11_11") (pintype "passive"))
    )
    (net (code "78") (name "P62") (class "Default")
      (node (ref "IC1") (pin "62") (pinfunction "RE2_62") (pintype "bidirectional"))
      (node (ref "SV3") (pin "14") (pinfunction "14_14") (pintype "passive"))
    )
    (net (code "79") (name "P63") (class "Default")
      (node (ref "IC1") (pin "63") (pinfunction "RE3_63") (pintype "bidirectional"))
      (node (ref "SV3") (pin "13") (pinfunction "13_13") (pintype "passive"))
    )
    (net (code "80") (name "P64") (class "Default")
      (node (ref "IC1") (pin "64") (pinfunction "RE4_64") (pintype "bidirectional"))
      (node (ref "SV3") (pin "16") (pinfunction "16_16") (pintype "passive"))
    )
    (net (code "81") (name "P201") (class "Default")
      (node (ref "IC3") (pin "34") (pinfunction "RA4_34") (pintype "bidirectional"))
      (node (ref "SV4") (pin "1") (pinfunction "1_1") (pintype "passive"))
    )
    (net (code "82") (name "P203") (class "Default")
      (node (ref "IC3") (pin "36") (pinfunction "RC3_36") (pintype "bidirectional"))
      (node (ref "SV4") (pin "3") (pinfunction "3_3") (pintype "passive"))
    )
    (net (code "83") (name "P204") (class "Default")
      (node (ref "IC3") (pin "35") (pinfunction "TDI_35") (pintype "input"))
      (node (ref "SV4") (pin "4") (pinfunction "4_4") (pintype "passive"))
    )
    (net (code "84") (name "P205") (class "Default")
      (node (ref "IC3") (pin "38") (pinfunction "RC5_38") (pintype "bidirectional"))
      (node (ref "SV4") (pin "5") (pinfunction "5_5") (pintype "passive"))
    )
    (net (code "85") (name "P206") (class "Default")
      (node (ref "IC3") (pin "37") (pinfunction "RC4_37") (pintype "bidirectional"))
      (node (ref "SV4") (pin "6") (pinfunction "6_6") (pintype "passive"))
    )
    (net (code "86") (name "P207") (class "Default")
      (node (ref "IC3") (pin "42") (pinfunction "RB6_42") (pintype "bidirectional"))
      (node (ref "SV4") (pin "7") (pinfunction "7_7") (pintype "passive"))
    )
    (net (code "87") (name "P208") (class "Default")
      (node (ref "IC3") (pin "41") (pinfunction "RB5_41") (pintype "bidirectional"))
      (node (ref "SV4") (pin "8") (pinfunction "8_8") (pintype "passive"))
    )
    (net (code "88") (name "P209") (class "Default")
      (node (ref "IC3") (pin "44") (pinfunction "RB8_44") (pintype "bidirectional"))
      (node (ref "SJ1") (pin "1") (pinfunction "1_1") (pintype "passive"))
      (node (ref "SV4") (pin "9") (pinfunction "9_9") (pintype "passive"))
    )
    (net (code "89") (name "P210") (class "Default")
      (node (ref "IC3") (pin "43") (pinfunction "RB7_43") (pintype "bidirectional"))
      (node (ref "SV4") (pin "10") (pinfunction "10_10") (pintype "passive"))
    )
    (net (code "90") (name "P211") (class "Default")
      (node (ref "IC3") (pin "2") (pinfunction "RC6_2") (pintype "bidirectional"))
      (node (ref "SV4") (pin "11") (pinfunction "11_11") (pintype "passive"))
    )
    (net (code "91") (name "P212") (class "Default")
      (node (ref "IC3") (pin "1") (pinfunction "RB9_1") (pintype "bidirectional"))
      (node (ref "SJ2") (pin "3") (pinfunction "3_3") (pintype "passive"))
      (node (ref "SV4") (pin "12") (pinfunction "12_12") (pintype "passive"))
    )
    (net (code "92") (name "P213") (class "Default")
      (node (ref "IC3") (pin "4") (pinfunction "RC8_4") (pintype "bidirectional"))
      (node (ref "SV4") (pin "13") (pinfunction "13_13") (pintype "passive"))
    )
    (net (code "93") (name "P214") (class "Default")
      (node (ref "IC3") (pin "3") (pinfunction "RC7_3") (pintype "bidirectional"))
      (node (ref "SV4") (pin "14") (pinfunction "14_14") (pintype "passive"))
    )
    (net (code "94") (name "P215") (class "Default")
      (node (ref "IC3") (pin "8") (pinfunction "RB10_8") (pintype "bidirectional"))
      (node (ref "SV4") (pin "15") (pinfunction "15_15") (pintype "passive"))
    )
    (net (code "95") (name "P216") (class "Default")
      (node (ref "IC3") (pin "5") (pinfunction "RC9_5") (pintype "bidirectional"))
      (node (ref "SV4") (pin "16") (pinfunction "16_16") (pintype "passive"))
    )
    (net (code "96") (name "P217") (class "Default")
      (node (ref "IC3") (pin "10") (pinfunction "RB12_10") (pintype "bidirectional"))
      (node (ref "SV4") (pin "17") (pinfunction "17_17") (pintype "passive"))
    )
    (net (code "97") (name "P218") (class "Default")
      (node (ref "IC3") (pin "9") (pinfunction "RB11_9") (pintype "bidirectional"))
      (node (ref "SV4") (pin "18") (pinfunction "18_18") (pintype "passive"))
    )
    (net (code "98") (name "P219") (class "Default")
      (node (ref "IC3") (pin "12") (pinfunction "TMS_12") (pintype "input"))
      (node (ref "SV4") (pin "19") (pinfunction "19_19") (pintype "passive"))
    )
    (net (code "99") (name "P220") (class "Default")
      (node (ref "IC3") (pin "11") (pinfunction "RB13_11") (pintype "bidirectional"))
      (node (ref "SV4") (pin "20") (pinfunction "20_20") (pintype "passive"))
    )
    (net (code "100") (name "P221") (class "Default")
      (node (ref "IC3") (pin "14") (pinfunction "RB14_14") (pintype "bidirectional"))
      (node (ref "SV5") (pin "1") (pinfunction "1_1") (pintype "passive"))
    )
    (net (code "101") (name "P222") (class "Default")
      (node (ref "IC3") (pin "13") (pinfunction "TCK_13") (pintype "input"))
      (node (ref "SV5") (pin "2") (pinfunction "2_2") (pintype "passive"))
    )
    (net (code "102") (name "P223") (class "Default")
      (node (ref "IC3") (pin "19") (pinfunction "RA0_19") (pintype "bidirectional"))
      (node (ref "SV5") (pin "3") (pinfunction "3_3") (pintype "passive"))
    )
    (net (code "103") (name "P224") (class "Default")
      (node (ref "IC3") (pin "15") (pinfunction "RB15_15") (pintype "bidirectional"))
      (node (ref "SV5") (pin "4") (pinfunction "4_4") (pintype "passive"))
    )
    (net (code "104") (name "P225") (class "Default")
      (node (ref "IC3") (pin "21") (pinfunction "RB0_21") (pintype "bidirectional"))
      (node (ref "SJ1") (pin "3") (pinfunction "3_3") (pintype "passive"))
      (node (ref "SV5") (pin "5") (pinfunction "5_5") (pintype "passive"))
    )
    (net (code "105") (name "P226") (class "Default")
      (node (ref "IC3") (pin "20") (pinfunction "RA1_20") (pintype "bidirectional"))
      (node (ref "SV5") (pin "6") (pinfunction "6_6") (pintype "passive"))
    )
    (net (code "106") (name "P227") (class "Default")
      (node (ref "IC3") (pin "23") (pinfunction "RB2_23") (pintype "bidirectional"))
      (node (ref "SV5") (pin "7") (pinfunction "7_7") (pintype "passive"))
    )
    (net (code "107") (name "P228") (class "Default")
      (node (ref "IC3") (pin "22") (pinfunction "RB1_22") (pintype "bidirectional"))
      (node (ref "SJ2") (pin "1") (pinfunction "1_1") (pintype "passive"))
      (node (ref "SV5") (pin "8") (pinfunction "8_8") (pintype "passive"))
    )
    (net (code "108") (name "P229") (class "Default")
      (node (ref "IC3") (pin "25") (pinfunction "RC0_25") (pintype "bidirectional"))
      (node (ref "SV5") (pin "9") (pinfunction "9_9") (pintype "passive"))
    )
    (net (code "109") (name "P230") (class "Default")
      (node (ref "IC3") (pin "24") (pinfunction "RB3_24") (pintype "bidirectional"))
      (node (ref "SV5") (pin "10") (pinfunction "10_10") (pintype "passive"))
    )
    (net (code "110") (name "P231") (class "Default")
      (node (ref "IC3") (pin "27") (pinfunction "RC2_27") (pintype "bidirectional"))
      (node (ref "SV5") (pin "11") (pinfunction "11_11") (pintype "passive"))
    )
    (net (code "111") (name "P232") (class "Default")
      (node (ref "IC3") (pin "26") (pinfunction "RC1_26") (pintype "bidirectional"))
      (node (ref "SV5") (pin "12") (pinfunction "12_12") (pintype "passive"))
    )
    (net (code "112") (name "P235") (class "Default")
      (node (ref "IC3") (pin "33") (pinfunction "RB4_33") (pintype "bidirectional"))
      (node (ref "SV5") (pin "15") (pinfunction "15_15") (pintype "passive"))
    )
    (net (code "113") (name "P236") (class "Default")
      (node (ref "IC3") (pin "32") (pinfunction "TDO_32") (pintype "output"))
      (node (ref "SV5") (pin "16") (pinfunction "16_16") (pintype "passive"))
    )
    (net (code "114") (name "P302") (class "Default")
      (node (ref "SV6") (pin "19") (pinfunction "19_19") (pintype "passive"))
      (node (ref "U2") (pin "62") (pinfunction "PB9-TIM4CH4-I2C1SDA/CANTX_62") (pintype "bidirectional"))
    )
    (net (code "115") (name "P303") (class "Default")
      (node (ref "SV6") (pin "20") (pinfunction "20_20") (pintype "passive"))
      (node (ref "U2") (pin "61") (pinfunction "PB8-TIM4CH3-I2C1SCL/CANRX_61") (pintype "bidirectional"))
    )
    (net (code "116") (name "P305") (class "Default")
      (node (ref "SV6") (pin "17") (pinfunction "17_17") (pintype "passive"))
      (node (ref "U2") (pin "60") (pinfunction "BOOT0_60") (pintype "input"))
    )
    (net (code "117") (name "P306") (class "Default")
      (node (ref "SV6") (pin "18") (pinfunction "18_18") (pintype "passive"))
      (node (ref "U2") (pin "59") (pinfunction "PB7-I2C1SDA/TIM4CH2-USART1RX_59") (pintype "bidirectional"))
    )
    (net (code "118") (name "P308") (class "Default")
      (node (ref "SV6") (pin "15") (pinfunction "15_15") (pintype "passive"))
      (node (ref "U2") (pin "58") (pinfunction "PB6-I2C1SCL/TIM4CH1-USART1TX_58") (pintype "bidirectional"))
    )
    (net (code "119") (name "P309") (class "Default")
      (node (ref "SV6") (pin "16") (pinfunction "16_16") (pintype "passive"))
      (node (ref "U2") (pin "57") (pinfunction "PB5-I2C1SMBAI-TIM3CH2/SPI1MOSI_57") (pintype "bidirectional"))
    )
    (net (code "120") (name "P311") (class "Default")
      (node (ref "SV6") (pin "13") (pinfunction "13_13") (pintype "passive"))
      (node (ref "U2") (pin "56") (pinfunction "PB4/JNTRST--TIM3CH1/SPI1MISO_56") (pintype "bidirectional"))
    )
    (net (code "121") (name "P312") (class "Default")
      (node (ref "SV6") (pin "14") (pinfunction "14_14") (pintype "passive"))
      (node (ref "U2") (pin "55") (pinfunction "PB3/JTDO--TIM2CH2/TRACESWO/SPI1SCK_55") (pintype "bidirectional"))
    )
    (net (code "122") (name "P314") (class "Default")
      (node (ref "SV6") (pin "11") (pinfunction "11_11") (pintype "passive"))
      (node (ref "U2") (pin "54") (pinfunction "PD2-TIM3ETR_54") (pintype "bidirectional"))
    )
    (net (code "123") (name "P315") (class "Default")
      (node (ref "SV6") (pin "12") (pinfunction "12_12") (pintype "passive"))
      (node (ref "U2") (pin "53") (pinfunction "PC12--USART3CK_53") (pintype "bidirectional"))
    )
    (net (code "124") (name "P317") (class "Default")
      (node (ref "SV6") (pin "9") (pinfunction "9_9") (pintype "passive"))
      (node (ref "U2") (pin "52") (pinfunction "PC11--USART3RX_52") (pintype "bidirectional"))
    )
    (net (code "125") (name "P318") (class "Default")
      (node (ref "SV6") (pin "10") (pinfunction "10_10") (pintype "passive"))
      (node (ref "U2") (pin "51") (pinfunction "PC10--USART3TX_51") (pintype "bidirectional"))
    )
    (net (code "126") (name "P320") (class "Default")
      (node (ref "SV6") (pin "7") (pinfunction "7_7") (pintype "passive"))
      (node (ref "U2") (pin "50") (pinfunction "PA15/JTDI-TIM2CH1ETR/SPI1NSS_50") (pintype "bidirectional"))
    )
    (net (code "127") (name "P321") (class "Default")
      (node (ref "SV6") (pin "8") (pinfunction "8_8") (pintype "passive"))
      (node (ref "U2") (pin "49") (pinfunction "PA14/JTCK/SWCLK_49") (pintype "bidirectional"))
    )
    (net (code "128") (name "P323") (class "Default")
      (node (ref "SV6") (pin "5") (pinfunction "5_5") (pintype "passive"))
      (node (ref "U2") (pin "46") (pinfunction "PA13/JTMS/SWDIO_46") (pintype "bidirectional"))
    )
    (net (code "129") (name "P324") (class "Default")
      (node (ref "SV6") (pin "6") (pinfunction "6_6") (pintype "passive"))
      (node (ref "U2") (pin "45") (pinfunction "PA12-USART1RTS/CANTX/USBDP/TIM1ETR_45") (pintype "bidirectional"))
    )
    (net (code "130") (name "P326") (class "Default")
      (node (ref "SV6") (pin "3") (pinfunction "3_3") (pintype "passive"))
      (node (ref "U2") (pin "44") (pinfunction "PA11-USART1CTS/CANRX/USBDM/TIM1CH4_44") (pintype "bidirectional"))
    )
    (net (code "131") (name "P327") (class "Default")
      (node (ref "SV6") (pin "4") (pinfunction "4_4") (pintype "passive"))
      (node (ref "U2") (pin "43") (pinfunction "PA10-USART1RX/TIM1CH3_43") (pintype "bidirectional"))
    )
    (net (code "132") (name "P329") (class "Default")
      (node (ref "SV6") (pin "1") (pinfunction "1_1") (pintype "passive"))
      (node (ref "U2") (pin "42") (pinfunction "PA9-USART1TX/TIM1CH2_42") (pintype "bidirectional"))
    )
    (net (code "133") (name "P330") (class "Default")
      (node (ref "SV6") (pin "2") (pinfunction "2_2") (pintype "passive"))
      (node (ref "U2") (pin "41") (pinfunction "PA8-USART1CK/MCO/TIM1CH1_41") (pintype "bidirectional"))
    )
    (net (code "134") (name "P332") (class "Default")
      (node (ref "SV7") (pin "19") (pinfunction "19_19") (pintype "passive"))
      (node (ref "U2") (pin "40") (pinfunction "PC9-TIM3CH4_40") (pintype "bidirectional"))
    )
    (net (code "135") (name "P333") (class "Default")
      (node (ref "SV7") (pin "20") (pinfunction "20_20") (pintype "passive"))
      (node (ref "U2") (pin "39") (pinfunction "PC8-TIM3CH3_39") (pintype "bidirectional"))
    )
    (net (code "136") (name "P335") (class "Default")
      (node (ref "SV7") (pin "17") (pinfunction "17_17") (pintype "passive"))
      (node (ref "U2") (pin "38") (pinfunction "PC7-TIM3CH2_38") (pintype "bidirectional"))
    )
    (net (code "137") (name "P336") (class "Default")
      (node (ref "SV7") (pin "18") (pinfunction "18_18") (pintype "passive"))
      (node (ref "U2") (pin "37") (pinfunction "PC6-TIM3CH1_37") (pintype "bidirectional"))
    )
    (net (code "138") (name "P338") (class "Default")
      (node (ref "SV7") (pin "15") (pinfunction "15_15") (pintype "passive"))
      (node (ref "U2") (pin "36") (pinfunction "PB15-SPI2MOSI/TIM1CH3N_36") (pintype "bidirectional"))
    )
    (net (code "139") (name "P339") (class "Default")
      (node (ref "SV7") (pin "16") (pinfunction "16_16") (pintype "passive"))
      (node (ref "U2") (pin "35") (pinfunction "PB14-SPI2MISO/USART3RTS/TIM1CH2N_35") (pintype "bidirectional"))
    )
    (net (code "140") (name "P341") (class "Default")
      (node (ref "SV7") (pin "13") (pinfunction "13_13") (pintype "passive"))
      (node (ref "U2") (pin "34") (pinfunction "PB13-SPI2SCK/USART3CTS/TIM1CH1N_34") (pintype "bidirectional"))
    )
    (net (code "141") (name "P342") (class "Default")
      (node (ref "SV7") (pin "14") (pinfunction "14_14") (pintype "passive"))
      (node (ref "U2") (pin "33") (pinfunction "PB12-SPI2NSS/I2C2SMBAI/USART3CK/TIM1BKIN_33") (pintype "bidirectional"))
    )
    (net (code "142") (name "P350") (class "Default")
      (node (ref "SV7") (pin "3") (pinfunction "3_3") (pintype "passive"))
      (node (ref "SV7") (pin "7") (pinfunction "7_7") (pintype "passive"))
      (node (ref "U2") (pin "29") (pinfunction "PB10-I2C2SCL/USART3TX-TIM2CH3_29") (pintype "bidirectional"))
    )
    (net (code "143") (name "P351") (class "Default")
      (node (ref "SV7") (pin "8") (pinfunction "8_8") (pintype "passive"))
      (node (ref "U2") (pin "30") (pinfunction "PB11-I2C2SDA/USART3RX-TIM2CH4_30") (pintype "bidirectional"))
    )
    (net (code "144") (name "P353") (class "Default")
      (node (ref "SV7") (pin "1") (pinfunction "1_1") (pintype "passive"))
      (node (ref "U2") (pin "27") (pinfunction "PB1-ADC9/TIM3CH4-TIM1CH3N_27") (pintype "bidirectional"))
    )
    (net (code "145") (name "P354") (class "Default")
      (node (ref "SV7") (pin "6") (pinfunction "6_6") (pintype "passive"))
      (node (ref "U2") (pin "28") (pinfunction "PB2/BOOT1_28") (pintype "bidirectional"))
    )
    (net (code "146") (name "P356") (class "Default")
      (node (ref "SV8") (pin "19") (pinfunction "19_19") (pintype "passive"))
      (node (ref "U2") (pin "25") (pinfunction "PC5-ADC15_25") (pintype "bidirectional"))
    )
    (net (code "147") (name "P357") (class "Default")
      (node (ref "SV7") (pin "4") (pinfunction "4_4") (pintype "passive"))
      (node (ref "U2") (pin "26") (pinfunction "PB0-ADC8/TIM3CH3-TIM1CH2N_26") (pintype "bidirectional"))
    )
    (net (code "148") (name "P359") (class "Default")
      (node (ref "SV8") (pin "17") (pinfunction "17_17") (pintype "passive"))
      (node (ref "U2") (pin "23") (pinfunction "PA7-SPI1MOSI/ADC7/TIM3CH2-TIM1CH1N_23") (pintype "bidirectional"))
    )
    (net (code "149") (name "P360") (class "Default")
      (node (ref "SV7") (pin "2") (pinfunction "2_2") (pintype "passive"))
      (node (ref "U2") (pin "24") (pinfunction "PC4-ADC14_24") (pintype "bidirectional"))
    )
    (net (code "150") (name "P362") (class "Default")
      (node (ref "SV8") (pin "15") (pinfunction "15_15") (pintype "passive"))
      (node (ref "U2") (pin "21") (pinfunction "PA5-SPI1SCK/ADC5_21") (pintype "bidirectional"))
    )
    (net (code "151") (name "P363") (class "Default")
      (node (ref "SV8") (pin "20") (pinfunction "20_20") (pintype "passive"))
      (node (ref "U2") (pin "22") (pinfunction "PA6-SPI1MISO/ADC6/TIM3CH1-TIM1BKIN_22") (pintype "bidirectional"))
    )
    (net (code "152") (name "P365") (class "Default")
      (node (ref "SV8") (pin "13") (pinfunction "13_13") (pintype "passive"))
      (node (ref "U2") (pin "17") (pinfunction "PA3-USART2RX/ADC3/TIM2CH4_17") (pintype "bidirectional"))
    )
    (net (code "153") (name "P366") (class "Default")
      (node (ref "SV8") (pin "18") (pinfunction "18_18") (pintype "passive"))
      (node (ref "U2") (pin "20") (pinfunction "PA4-SPI1NSS/ADC4/USART2CK_20") (pintype "bidirectional"))
    )
    (net (code "154") (name "P368") (class "Default")
      (node (ref "SV8") (pin "11") (pinfunction "11_11") (pintype "passive"))
      (node (ref "U2") (pin "15") (pinfunction "PA1-USART2RTS/ADC1/TIM2CH2_15") (pintype "bidirectional"))
    )
    (net (code "155") (name "P369") (class "Default")
      (node (ref "SV8") (pin "16") (pinfunction "16_16") (pintype "passive"))
      (node (ref "U2") (pin "16") (pinfunction "PA2-USART2TX/ADC2/TIM2CH3_16") (pintype "bidirectional"))
    )
    (net (code "156") (name "P371") (class "Default")
      (node (ref "SV8") (pin "9") (pinfunction "9_9") (pintype "passive"))
      (node (ref "U2") (pin "11") (pinfunction "PC3-ADC13_11") (pintype "bidirectional"))
    )
    (net (code "157") (name "P372") (class "Default")
      (node (ref "SV8") (pin "14") (pinfunction "14_14") (pintype "passive"))
      (node (ref "U2") (pin "14") (pinfunction "PA0-WKUP/USART2CTS/ADC0/TIM2CH1ETR_14") (pintype "bidirectional"))
    )
    (net (code "158") (name "P374") (class "Default")
      (node (ref "SV8") (pin "7") (pinfunction "7_7") (pintype "passive"))
      (node (ref "U2") (pin "9") (pinfunction "PC1-ADC11_9") (pintype "bidirectional"))
    )
    (net (code "159") (name "P375") (class "Default")
      (node (ref "SV8") (pin "12") (pinfunction "12_12") (pintype "passive"))
      (node (ref "U2") (pin "10") (pinfunction "PC2-ADC12_10") (pintype "bidirectional"))
    )
    (net (code "160") (name "P378") (class "Default")
      (node (ref "SV8") (pin "10") (pinfunction "10_10") (pintype "passive"))
      (node (ref "U2") (pin "8") (pinfunction "PC0-ADC10_8") (pintype "bidirectional"))
    )
    (net (code "161") (name "P380") (class "Default")
      (node (ref "SV8") (pin "3") (pinfunction "3_3") (pintype "passive"))
      (node (ref "U2") (pin "4") (pinfunction "PC15-OSC32_OUT_4") (pintype "bidirectional"))
    )
    (net (code "162") (name "P383") (class "Default")
      (node (ref "SV8") (pin "1") (pinfunction "1_1") (pintype "passive"))
      (node (ref "U2") (pin "2") (pinfunction "PC13-TAMPER-RTC_2") (pintype "bidirectional"))
    )
    (net (code "163") (name "P384") (class "Default")
      (node (ref "SV8") (pin "6") (pinfunction "6_6") (pintype "passive"))
      (node (ref "U2") (pin "3") (pinfunction "PC14-OSC32_IN_3") (pintype "bidirectional"))
    )
    (net (code "164") (name "P387") (class "Default")
      (node (ref "SV8") (pin "4") (pinfunction "4_4") (pintype "passive"))
    )
    (net (code "165") (name "P401") (class "Default")
      (node (ref "IC4") (pin "35") (pinfunction "RC1/SOSCI/CCP2_35") (pintype "bidirectional"))
      (node (ref "SV9") (pin "1") (pinfunction "1_1") (pintype "passive"))
    )
    (net (code "166") (name "P403") (class "Default")
      (node (ref "IC4") (pin "37") (pinfunction "RC3/AN15/SCK/SCL_37") (pintype "bidirectional"))
      (node (ref "SV9") (pin "3") (pinfunction "3_3") (pintype "passive"))
    )
    (net (code "167") (name "P404") (class "Default")
      (node (ref "IC4") (pin "36") (pinfunction "RC2/AN14/CCP1_36") (pintype "bidirectional"))
      (node (ref "SV9") (pin "4") (pinfunction "4_4") (pintype "passive"))
    )
    (net (code "168") (name "P405") (class "Default")
      (node (ref "IC4") (pin "39") (pinfunction "RD1/AN21_39") (pintype "bidirectional"))
      (node (ref "SV9") (pin "5") (pinfunction "5_5") (pintype "passive"))
    )
    (net (code "169") (name "P406") (class "Default")
      (node (ref "IC4") (pin "38") (pinfunction "RD0/AN20_38") (pintype "bidirectional"))
      (node (ref "SV9") (pin "6") (pinfunction "6_6") (pintype "passive"))
    )
    (net (code "170") (name "P407") (class "Default")
      (node (ref "IC4") (pin "41") (pinfunction "RD3/AN23_41") (pintype "bidirectional"))
      (node (ref "SV9") (pin "7") (pinfunction "7_7") (pintype "passive"))
    )
    (net (code "171") (name "P408") (class "Default")
      (node (ref "IC4") (pin "40") (pinfunction "RD2/AN22_40") (pintype "bidirectional"))
      (node (ref "SV9") (pin "8") (pinfunction "8_8") (pintype "passive"))
    )
    (net (code "172") (name "P409") (class "Default")
      (node (ref "IC4") (pin "43") (pinfunction "RC5/AN17/SDO_43") (pintype "bidirectional"))
      (node (ref "SV9") (pin "9") (pinfunction "9_9") (pintype "passive"))
    )
    (net (code "173") (name "P410") (class "Default")
      (node (ref "IC4") (pin "42") (pinfunction "RC4/AN16/SDI/SDA_42") (pintype "bidirectional"))
      (node (ref "SV9") (pin "10") (pinfunction "10_10") (pintype "passive"))
    )
    (net (code "174") (name "P411") (class "Default")
      (node (ref "IC4") (pin "1") (pinfunction "DT/RX/AN19/RC7_1") (pintype "bidirectional"))
      (node (ref "SV9") (pin "11") (pinfunction "11_11") (pintype "passive"))
    )
    (net (code "175") (name "P412") (class "Default")
      (node (ref "IC4") (pin "44") (pinfunction "RC6/AN18/TX/CK_44") (pintype "bidirectional"))
      (node (ref "SV9") (pin "12") (pinfunction "12_12") (pintype "passive"))
    )
    (net (code "176") (name "P413") (class "Default")
      (node (ref "IC4") (pin "3") (pinfunction "AN25/RD5_3") (pintype "bidirectional"))
      (node (ref "SV9") (pin "13") (pinfunction "13_13") (pintype "passive"))
    )
    (net (code "177") (name "P414") (class "Default")
      (node (ref "IC4") (pin "2") (pinfunction "AN24/RD4_2") (pintype "bidirectional"))
      (node (ref "SV9") (pin "14") (pinfunction "14_14") (pintype "passive"))
    )
    (net (code "178") (name "P415") (class "Default")
      (node (ref "IC4") (pin "5") (pinfunction "AN27/RD7_5") (pintype "bidirectional"))
      (node (ref "SV9") (pin "15") (pinfunction "15_15") (pintype "passive"))
    )
    (net (code "179") (name "P416") (class "Default")
      (node (ref "IC4") (pin "4") (pinfunction "AN26/RD6_4") (pintype "bidirectional"))
      (node (ref "SV9") (pin "16") (pinfunction "16_16") (pintype "passive"))
    )
    (net (code "180") (name "P417") (class "Default")
      (node (ref "IC4") (pin "9") (pinfunction "AN10/RB1_9") (pintype "bidirectional"))
      (node (ref "SV9") (pin "17") (pinfunction "17_17") (pintype "passive"))
    )
    (net (code "181") (name "P418") (class "Default")
      (node (ref "IC4") (pin "8") (pinfunction "INT/AN12/RB0_8") (pintype "bidirectional"))
      (node (ref "SV9") (pin "18") (pinfunction "18_18") (pintype "passive"))
    )
    (net (code "182") (name "P419") (class "Default")
      (node (ref "IC4") (pin "11") (pinfunction "CCP2/AN9/RB3_11") (pintype "bidirectional"))
      (node (ref "SV9") (pin "19") (pinfunction "19_19") (pintype "passive"))
    )
    (net (code "183") (name "P420") (class "Default")
      (node (ref "IC4") (pin "10") (pinfunction "AN8/RB2_10") (pintype "bidirectional"))
      (node (ref "SV9") (pin "20") (pinfunction "20_20") (pintype "passive"))
    )
    (net (code "184") (name "P421") (class "Default")
      (node (ref "IC4") (pin "14") (pinfunction "AN11/RB4_14") (pintype "bidirectional"))
      (node (ref "SV10") (pin "1") (pinfunction "1_1") (pintype "passive"))
    )
    (net (code "185") (name "P422") (class "Default")
      (node (ref "IC4") (pin "15") (pinfunction "T1G/AN13/RB5_15") (pintype "bidirectional"))
      (node (ref "SV10") (pin "2") (pinfunction "2_2") (pintype "passive"))
    )
    (net (code "186") (name "P425") (class "Default")
      (node (ref "IC4") (pin "19") (pinfunction "~{SS}/AN0/RA0_19") (pintype "bidirectional"))
      (node (ref "SV10") (pin "5") (pinfunction "5_5") (pintype "passive"))
    )
    (net (code "187") (name "P426") (class "Default")
      (node (ref "IC4") (pin "20") (pinfunction "AN1/RA1_20") (pintype "bidirectional"))
      (node (ref "SV10") (pin "6") (pinfunction "6_6") (pintype "passive"))
    )
    (net (code "188") (name "P427") (class "Default")
      (node (ref "IC4") (pin "21") (pinfunction "AN2/RA2_21") (pintype "bidirectional"))
      (node (ref "SV10") (pin "7") (pinfunction "7_7") (pintype "passive"))
    )
    (net (code "189") (name "P428") (class "Default")
      (node (ref "IC4") (pin "22") (pinfunction "VREF+/AN3/RA3_22") (pintype "bidirectional"))
      (node (ref "SV10") (pin "8") (pinfunction "8_8") (pintype "passive"))
    )
    (net (code "190") (name "P429") (class "Default")
      (node (ref "IC4") (pin "23") (pinfunction "RA4/TOCKI_23") (pintype "bidirectional"))
      (node (ref "SJ3") (pin "2") (pinfunction "2_2") (pintype "passive"))
      (node (ref "SV10") (pin "9") (pinfunction "9_9") (pintype "passive"))
    )
    (net (code "191") (name "P430") (class "Default")
      (node (ref "IC4") (pin "24") (pinfunction "RA5/AN4/~{SS}/VCAP_24") (pintype "bidirectional"))
      (node (ref "SV10") (pin "10") (pinfunction "10_10") (pintype "passive"))
    )
    (net (code "192") (name "P431") (class "Default")
      (node (ref "IC4") (pin "25") (pinfunction "RE0/AN5_25") (pintype "bidirectional"))
      (node (ref "SV10") (pin "11") (pinfunction "11_11") (pintype "passive"))
    )
    (net (code "193") (name "P432") (class "Default")
      (node (ref "IC4") (pin "26") (pinfunction "RE1/AN6_26") (pintype "bidirectional"))
      (node (ref "SV10") (pin "12") (pinfunction "12_12") (pintype "passive"))
    )
    (net (code "194") (name "P433") (class "Default")
      (node (ref "IC4") (pin "27") (pinfunction "RE2/AN7_27") (pintype "bidirectional"))
      (node (ref "SV10") (pin "13") (pinfunction "13_13") (pintype "passive"))
    )
    (net (code "195") (name "P436") (class "Default")
      (node (ref "IC4") (pin "32") (pinfunction "RC0/SOSCO/T1CKI_32") (pintype "bidirectional"))
      (node (ref "SV10") (pin "16") (pinfunction "16_16") (pintype "passive"))
    )
    (net (code "196") (name "P502") (class "Default")
      (node (ref "SV11") (pin "2") (pinfunction "2_2") (pintype "passive"))
    )
    (net (code "197") (name "P504") (class "Default")
      (node (ref "SV11") (pin "4") (pinfunction "4_4") (pintype "passive"))
    )
    (net (code "198") (name "P506") (class "Default")
      (node (ref "SV11") (pin "6") (pinfunction "6_6") (pintype "passive"))
    )
    (net (code "199") (name "P507") (class "Default")
      (node (ref "IC6") (pin "3") (pinfunction "3_3") (pintype "passive"))
      (node (ref "SV11") (pin "7") (pinfunction "7_7") (pintype "passive"))
    )
    (net (code "200") (name "P508") (class "Default")
      (node (ref "SV11") (pin "8") (pinfunction "8_8") (pintype "passive"))
    )
    (net (code "201") (name "P513") (class "Default")
      (node (ref "IC2") (pin "5") (pinfunction "5_5") (pintype "passive"))
      (node (ref "SV11") (pin "13") (pinfunction "13_13") (pintype "passive"))
    )
    (net (code "202") (name "P514") (class "Default")
      (node (ref "SV11") (pin "14") (pinfunction "14_14") (pintype "passive"))
    )
    (net (code "203") (name "P516") (class "Default")
      (node (ref "SV11") (pin "16") (pinfunction "16_16") (pintype "passive"))
    )
    (net (code "204") (name "P517") (class "Default")
      (node (ref "IC2") (pin "3") (pinfunction "3_3") (pintype "passive"))
      (node (ref "SV11") (pin "17") (pinfunction "17_17") (pintype "passive"))
    )
    (net (code "205") (name "P518") (class "Default")
      (node (ref "IC2") (pin "2") (pinfunction "2_2") (pintype "passive"))
      (node (ref "SV11") (pin "18") (pinfunction "18_18") (pintype "passive"))
    )
    (net (code "206") (name "P521") (class "Default")
      (node (ref "IC5") (pin "8") (pinfunction "8_8") (pintype "passive"))
      (node (ref "SV12") (pin "1") (pinfunction "1_1") (pintype "passive"))
    )
    (net (code "207") (name "P522") (class "Default")
      (node (ref "IC5") (pin "7") (pinfunction "7_7") (pintype "passive"))
      (node (ref "SV12") (pin "2") (pinfunction "2_2") (pintype "passive"))
    )
    (net (code "208") (name "P523") (class "Default")
      (node (ref "IC5") (pin "9") (pinfunction "9_9") (pintype "passive"))
      (node (ref "SV12") (pin "3") (pinfunction "3_3") (pintype "passive"))
    )
    (net (code "209") (name "P524") (class "Default")
      (node (ref "IC5") (pin "6") (pinfunction "6_6") (pintype "passive"))
      (node (ref "SV12") (pin "4") (pinfunction "4_4") (pintype "passive"))
    )
    (net (code "210") (name "P525") (class "Default")
      (node (ref "IC5") (pin "10") (pinfunction "10_10") (pintype "passive"))
      (node (ref "SV12") (pin "5") (pinfunction "5_5") (pintype "passive"))
    )
    (net (code "211") (name "P526") (class "Default")
      (node (ref "IC5") (pin "5") (pinfunction "5_5") (pintype "passive"))
      (node (ref "SV12") (pin "6") (pinfunction "6_6") (pintype "passive"))
    )
    (net (code "212") (name "P527") (class "Default")
      (node (ref "IC5") (pin "11") (pinfunction "11_11") (pintype "passive"))
      (node (ref "SV12") (pin "7") (pinfunction "7_7") (pintype "passive"))
    )
    (net (code "213") (name "P533") (class "Default")
      (node (ref "SV12") (pin "13") (pinfunction "13_13") (pintype "passive"))
    )
    (net (code "214") (name "P534") (class "Default")
      (node (ref "SV12") (pin "14") (pinfunction "14_14") (pintype "passive"))
    )
    (net (code "215") (name "P535") (class "Default")
      (node (ref "SV12") (pin "15") (pinfunction "15_15") (pintype "passive"))
    )
    (net (code "216") (name "P536") (class "Default")
      (node (ref "SV12") (pin "16") (pinfunction "16_16") (pintype "passive"))
    )
    (net (code "217") (name "PGC") (class "Default")
      (node (ref "IC1") (pin "17") (pinfunction "RB6_17") (pintype "bidirectional"))
      (node (ref "JP4") (pin "5") (pinfunction "5_5") (pintype "passive"))
      (node (ref "SV2") (pin "11") (pinfunction "11_11") (pintype "passive"))
    )
    (net (code "218") (name "PGD") (class "Default")
      (node (ref "IC1") (pin "18") (pinfunction "RB7_18") (pintype "bidirectional"))
      (node (ref "JP4") (pin "4") (pinfunction "4_4") (pintype "passive"))
      (node (ref "SV2") (pin "12") (pinfunction "12_12") (pintype "passive"))
    )
    (net (code "219") (name "VCAP") (class "Default")
      (node (ref "IC1") (pin "56") (pinfunction "VDDCORE_56") (pintype "power_in"))
      (node (ref "JMP1") (pin "2") (pinfunction "2_2") (pintype "passive"))
    )
    (net (code "220") (name "VCC") (class "Default")
      (node (ref "C10") (pin "1") (pinfunction "1_1") (pintype "passive"))
      (node (ref "C11") (pin "1") (pinfunction "1_1") (pintype "passive"))
      (node (ref "C12") (pin "1") (pinfunction "1_1") (pintype "passive"))
      (node (ref "C15") (pin "1") (pinfunction "1_1") (pintype "passive"))
      (node (ref "C16") (pin "1") (pinfunction "1_1") (pintype "passive"))
      (node (ref "C17") (pin "1") (pinfunction "1_1") (pintype "passive"))
      (node (ref "C18") (pin "1") (pinfunction "1_1") (pintype "passive"))
      (node (ref "C2") (pin "1") (pinfunction "1_1") (pintype "passive"))
      (node (ref "C22") (pin "1") (pinfunction "1_1") (pintype "passive"))
      (node (ref "C23") (pin "1") (pinfunction "1_1") (pintype "passive"))
      (node (ref "C24") (pin "1") (pinfunction "1_1") (pintype "passive"))
      (node (ref "C25") (pin "+") (pinfunction "+_+") (pintype "passive"))
      (node (ref "C27") (pin "1") (pinfunction "1_1") (pintype "passive"))
      (node (ref "C28") (pin "1") (pinfunction "1_1") (pintype "passive"))
      (node (ref "C3") (pin "1") (pinfunction "1_1") (pintype "passive"))
      (node (ref "C32") (pin "1") (pinfunction "1_1") (pintype "passive"))
      (node (ref "C35") (pin "1") (pinfunction "1_1") (pintype "passive"))
      (node (ref "C36") (pin "1") (pinfunction "1_1") (pintype "passive"))
      (node (ref "C6") (pin "1") (pinfunction "1_1") (pintype "passive"))
      (node (ref "C7") (pin "1") (pinfunction "1_1") (pintype "passive"))
      (node (ref "C8") (pin "1") (pinfunction "1_1") (pintype "passive"))
      (node (ref "C9") (pin "+") (pinfunction "+_+") (pintype "passive"))
      (node (ref "IC1") (pin "10") (pinfunction "VDD_10") (pintype "power_in"))
      (node (ref "IC1") (pin "19") (pinfunction "AVDD_19") (pintype "power_in"))
      (node (ref "IC1") (pin "26") (pinfunction "VDD_26") (pintype "power_in"))
      (node (ref "IC1") (pin "38") (pinfunction "VDD_38") (pintype "power_in"))
      (node (ref "IC1") (pin "57") (pinfunction "VREG_57") (pintype "passive"))
      (node (ref "IC2") (pin "1") (pinfunction "1_1") (pintype "passive"))
      (node (ref "IC3") (pin "17") (pinfunction "AVDD_17") (pintype "power_in"))
      (node (ref "IC3") (pin "28") (pinfunction "VDD_28") (pintype "power_in"))
      (node (ref "IC3") (pin "40") (pinfunction "VDD_40") (pintype "power_in"))
      (node (ref "IC3") (pin "7") (pinfunction "VDDCORE_7") (pintype "power_in"))
      (node (ref "IC4") (pin "28") (pinfunction "VDD_28") (pintype "power_in"))
      (node (ref "IC4") (pin "7") (pinfunction "VDD_7") (pintype "power_in"))
      (node (ref "IC5") (pin "1") (pinfunction "1_1") (pintype "passive"))
      (node (ref "IC6") (pin "2") (pinfunction "2_2") (pintype "passive"))
      (node (ref "JP1") (pin "2") (pinfunction "2_2") (pintype "passive"))
      (node (ref "JP2") (pin "2") (pinfunction "2_2") (pintype "passive"))
      (node (ref "JP3") (pin "2") (pinfunction "2_2") (pintype "passive"))
      (node (ref "JP4") (pin "2") (pinfunction "2_2") (pintype "passive"))
      (node (ref "R1") (pin "2") (pinfunction "2_2") (pintype "passive"))
      (node (ref "R2") (pin "2") (pinfunction "2_2") (pintype "passive"))
      (node (ref "R3") (pin "2") (pinfunction "2_2") (pintype "passive"))
      (node (ref "R4") (pin "2") (pinfunction "2_2") (pintype "passive"))
      (node (ref "R5") (pin "2") (pinfunction "2_2") (pintype "passive"))
      (node (ref "R6") (pin "2") (pinfunction "2_2") (pintype "passive"))
      (node (ref "R7") (pin "2") (pinfunction "2_2") (pintype "passive"))
      (node (ref "R8") (pin "2") (pinfunction "2_2") (pintype "passive"))
      (node (ref "R9") (pin "2") (pinfunction "2_2") (pintype "passive"))
      (node (ref "SJ3") (pin "1") (pinfunction "1_1") (pintype "passive"))
      (node (ref "SV1") (pin "17") (pinfunction "17_17") (pintype "passive"))
      (node (ref "SV1") (pin "18") (pinfunction "18_18") (pintype "passive"))
      (node (ref "SV10") (pin "17") (pinfunction "17_17") (pintype "passive"))
      (node (ref "SV10") (pin "18") (pinfunction "18_18") (pintype "passive"))
      (node (ref "SV11") (pin "10") (pinfunction "10_10") (pintype "passive"))
      (node (ref "SV11") (pin "19") (pinfunction "19_19") (pintype "passive"))
      (node (ref "SV11") (pin "20") (pinfunction "20_20") (pintype "passive"))
      (node (ref "SV11") (pin "9") (pinfunction "9_9") (pintype "passive"))
      (node (ref "SV12") (pin "17") (pinfunction "17_17") (pintype "passive"))
      (node (ref "SV12") (pin "18") (pinfunction "18_18") (pintype "passive"))
      (node (ref "SV2") (pin "10") (pinfunction "10_10") (pintype "passive"))
      (node (ref "SV2") (pin "9") (pinfunction "9_9") (pintype "passive"))
      (node (ref "SV5") (pin "17") (pinfunction "17_17") (pintype "passive"))
      (node (ref "SV5") (pin "18") (pinfunction "18_18") (pintype "passive"))
      (node (ref "SV7") (pin "10") (pinfunction "10_10") (pintype "passive"))
      (node (ref "SV7") (pin "12") (pinfunction "12_12") (pintype "passive"))
      (node (ref "SV7") (pin "5") (pinfunction "5_5") (pintype "passive"))
      (node (ref "U$3") (pin "1") (pinfunction "P$1_1") (pintype "passive"))
      (node (ref "U$3") (pin "2") (pinfunction "P$2_2") (pintype "passive"))
      (node (ref "U2") (pin "1") (pinfunction "VBAT_1") (pintype "power_in"))
      (node (ref "U2") (pin "13") (pinfunction "VDDA_13") (pintype "power_in"))
      (node (ref "U2") (pin "19") (pinfunction "VDD4_19") (pintype "bidirectional"))
      (node (ref "U2") (pin "32") (pinfunction "VDD1_32") (pintype "power_in"))
      (node (ref "U2") (pin "48") (pinfunction "VDD2_48") (pintype "power_in"))
      (node (ref "U2") (pin "64") (pinfunction "VDD3_64") (pintype "power_in"))
    )
    (net (code "221") (name "VSS") (class "Default")
      (node (ref "C1") (pin "-") (pinfunction "-_-") (pintype "passive"))
      (node (ref "C10") (pin "2") (pinfunction "2_2") (pintype "passive"))
      (node (ref "C11") (pin "2") (pinfunction "2_2") (pintype "passive"))
      (node (ref "C12") (pin "2") (pinfunction "2_2") (pintype "passive"))
      (node (ref "C13") (pin "2") (pinfunction "2_2") (pintype "passive"))
      (node (ref "C14") (pin "2") (pinfunction "2_2") (pintype "passive"))
      (node (ref "C15") (pin "2") (pinfunction "2_2") (pintype "passive"))
      (node (ref "C16") (pin "2") (pinfunction "2_2") (pintype "passive"))
      (node (ref "C17") (pin "2") (pinfunction "2_2") (pintype "passive"))
      (node (ref "C18") (pin "2") (pinfunction "2_2") (pintype "passive"))
      (node (ref "C19") (pin "2") (pinfunction "2_2") (pintype "passive"))
      (node (ref "C2") (pin "2") (pinfunction "2_2") (pintype "passive"))
      (node (ref "C20") (pin "2") (pinfunction "2_2") (pintype "passive"))
      (node (ref "C21") (pin "2") (pinfunction "2_2") (pintype "passive"))
      (node (ref "C22") (pin "2") (pinfunction "2_2") (pintype "passive"))
      (node (ref "C23") (pin "2") (pinfunction "2_2") (pintype "passive"))
      (node (ref "C24") (pin "2") (pinfunction "2_2") (pintype "passive"))
      (node (ref "C25") (pin "-") (pinfunction "-_-") (pintype "passive"))
      (node (ref "C26") (pin "2") (pinfunction "2_2") (pintype "passive"))
      (node (ref "C27") (pin "2") (pinfunction "2_2") (pintype "passive"))
      (node (ref "C28") (pin "2") (pinfunction "2_2") (pintype "passive"))
      (node (ref "C29") (pin "2") (pinfunction "2_2") (pintype "passive"))
      (node (ref "C3") (pin "2") (pinfunction "2_2") (pintype "passive"))
      (node (ref "C30") (pin "2") (pinfunction "2_2") (pintype "passive"))
      (node (ref "C31") (pin "2") (pinfunction "2_2") (pintype "passive"))
      (node (ref "C32") (pin "2") (pinfunction "2_2") (pintype "passive"))
      (node (ref "C33") (pin "2") (pinfunction "2_2") (pintype "passive"))
      (node (ref "C34") (pin "2") (pinfunction "2_2") (pintype "passive"))
      (node (ref "C35") (pin "2") (pinfunction "2_2") (pintype "passive"))
      (node (ref "C36") (pin "2") (pinfunction "2_2") (pintype "passive"))
      (node (ref "C4") (pin "2") (pinfunction "2_2") (pintype "passive"))
      (node (ref "C5") (pin "2") (pinfunction "2_2") (pintype "passive"))
      (node (ref "C6") (pin "2") (pinfunction "2_2") (pintype "passive"))
      (node (ref "C7") (pin "2") (pinfunction "2_2") (pintype "passive"))
      (node (ref "C8") (pin "2") (pinfunction "2_2") (pintype "passive"))
      (node (ref "C9") (pin "-") (pinfunction "-_-") (pintype "passive"))
      (node (ref "IC1") (pin "20") (pinfunction "AVSS_20") (pintype "power_in"))
      (node (ref "IC1") (pin "25") (pinfunction "VSS_25") (pintype "power_in"))
      (node (ref "IC1") (pin "41") (pinfunction "VSS_41") (pintype "power_in"))
      (node (ref "IC1") (pin "9") (pinfunction "VSS_9") (pintype "power_in"))
      (node (ref "IC2") (pin "8") (pinfunction "8_8") (pintype "passive"))
      (node (ref "IC3") (pin "16") (pinfunction "AVSS_16") (pintype "power_in"))
      (node (ref "IC3") (pin "29") (pinfunction "VSS_29") (pintype "power_in"))
      (node (ref "IC3") (pin "39") (pinfunction "VSS_39") (pintype "power_in"))
      (node (ref "IC3") (pin "6") (pinfunction "DISVREG_6") (pintype "passive"))
      (node (ref "IC4") (pin "29") (pinfunction "VSS_29") (pintype "power_in"))
      (node (ref "IC4") (pin "6") (pinfunction "VSS_6") (pintype "power_in"))
      (node (ref "IC5") (pin "14") (pinfunction "14_14") (pintype "passive"))
      (node (ref "IC6") (pin "7") (pinfunction "7_7") (pintype "passive"))
      (node (ref "JMP1") (pin "3") (pinfunction "3_3") (pintype "passive"))
      (node (ref "JP1") (pin "3") (pinfunction "3_3") (pintype "passive"))
      (node (ref "JP2") (pin "3") (pinfunction "3_3") (pintype "passive"))
      (node (ref "JP3") (pin "3") (pinfunction "3_3") (pintype "passive"))
      (node (ref "JP4") (pin "3") (pinfunction "3_3") (pintype "passive"))
      (node (ref "LED1") (pin "C") (pinfunction "C_C") (pintype "passive"))
      (node (ref "LED2") (pin "C") (pinfunction "C_C") (pintype "passive"))
      (node (ref "LED3") (pin "C") (pinfunction "C_C") (pintype "passive"))
      (node (ref "LED4") (pin "C") (pinfunction "C_C") (pintype "passive"))
      (node (ref "LED5") (pin "C") (pinfunction "C_C") (pintype "passive"))
      (node (ref "S1") (pin "3") (pinfunction "P_3") (pintype "passive"))
      (node (ref "S2") (pin "3") (pinfunction "P_3") (pintype "passive"))
      (node (ref "S3") (pin "3") (pinfunction "P_3") (pintype "passive"))
      (node (ref "S4") (pin "3") (pinfunction "P_3") (pintype "passive"))
      (node (ref "S5") (pin "3") (pinfunction "P_3") (pintype "passive"))
      (node (ref "SV1") (pin "19") (pinfunction "19_19") (pintype "passive"))
      (node (ref "SV1") (pin "20") (pinfunction "20_20") (pintype "passive"))
      (node (ref "SV10") (pin "19") (pinfunction "19_19") (pintype "passive"))
      (node (ref "SV10") (pin "20") (pinfunction "20_20") (pintype "passive"))
      (node (ref "SV12") (pin "19") (pinfunction "19_19") (pintype "passive"))
      (node (ref "SV12") (pin "20") (pinfunction "20_20") (pintype "passive"))
      (node (ref "SV5") (pin "19") (pinfunction "19_19") (pintype "passive"))
      (node (ref "SV5") (pin "20") (pinfunction "20_20") (pintype "passive"))
      (node (ref "U$3") (pin "3") (pinfunction "P$3_3") (pintype "passive"))
      (node (ref "U$3") (pin "4") (pinfunction "P$4_4") (pintype "passive"))
      (node (ref "U2") (pin "12") (pinfunction "VSSA_12") (pintype "power_in"))
      (node (ref "U2") (pin "18") (pinfunction "VSS4_18") (pintype "bidirectional"))
      (node (ref "U2") (pin "31") (pinfunction "VSS1_31") (pintype "power_in"))
      (node (ref "U2") (pin "47") (pinfunction "VSS2_47") (pintype "power_in"))
      (node (ref "U2") (pin "63") (pinfunction "VSS3_63") (pintype "power_in"))
    )
    (net (code "222") (name "unconnected-(S1-P1-Pad4)") (class "Default")
      (node (ref "S1") (pin "4") (pinfunction "P1_4") (pintype "passive"))
    )
    (net (code "223") (name "unconnected-(S1-S1-Pad2)") (class "Default")
      (node (ref "S1") (pin "2") (pinfunction "S1_2") (pintype "passive"))
    )
    (net (code "224") (name "unconnected-(S2-P1-Pad4)") (class "Default")
      (node (ref "S2") (pin "4") (pinfunction "P1_4") (pintype "passive"))
    )
    (net (code "225") (name "unconnected-(S2-S1-Pad2)") (class "Default")
      (node (ref "S2") (pin "2") (pinfunction "S1_2") (pintype "passive"))
    )
    (net (code "226") (name "unconnected-(S3-P1-Pad4)") (class "Default")
      (node (ref "S3") (pin "4") (pinfunction "P1_4") (pintype "passive"))
    )
    (net (code "227") (name "unconnected-(S3-S1-Pad2)") (class "Default")
      (node (ref "S3") (pin "2") (pinfunction "S1_2") (pintype "passive"))
    )
    (net (code "228") (name "unconnected-(S4-P1-Pad4)") (class "Default")
      (node (ref "S4") (pin "4") (pinfunction "P1_4") (pintype "passive"))
    )
    (net (code "229") (name "unconnected-(S4-S1-Pad2)") (class "Default")
      (node (ref "S4") (pin "2") (pinfunction "S1_2") (pintype "passive"))
    )
    (net (code "230") (name "unconnected-(S5-P1-Pad4)") (class "Default")
      (node (ref "S5") (pin "4") (pinfunction "P1_4") (pintype "passive"))
    )
    (net (code "231") (name "unconnected-(S5-S1-Pad2)") (class "Default")
      (node (ref "S5") (pin "2") (pinfunction "S1_2") (pintype "passive"))
    )
  )
)
